# Backplane.net
KiCad netlist of a schematic drawn in EAGLE
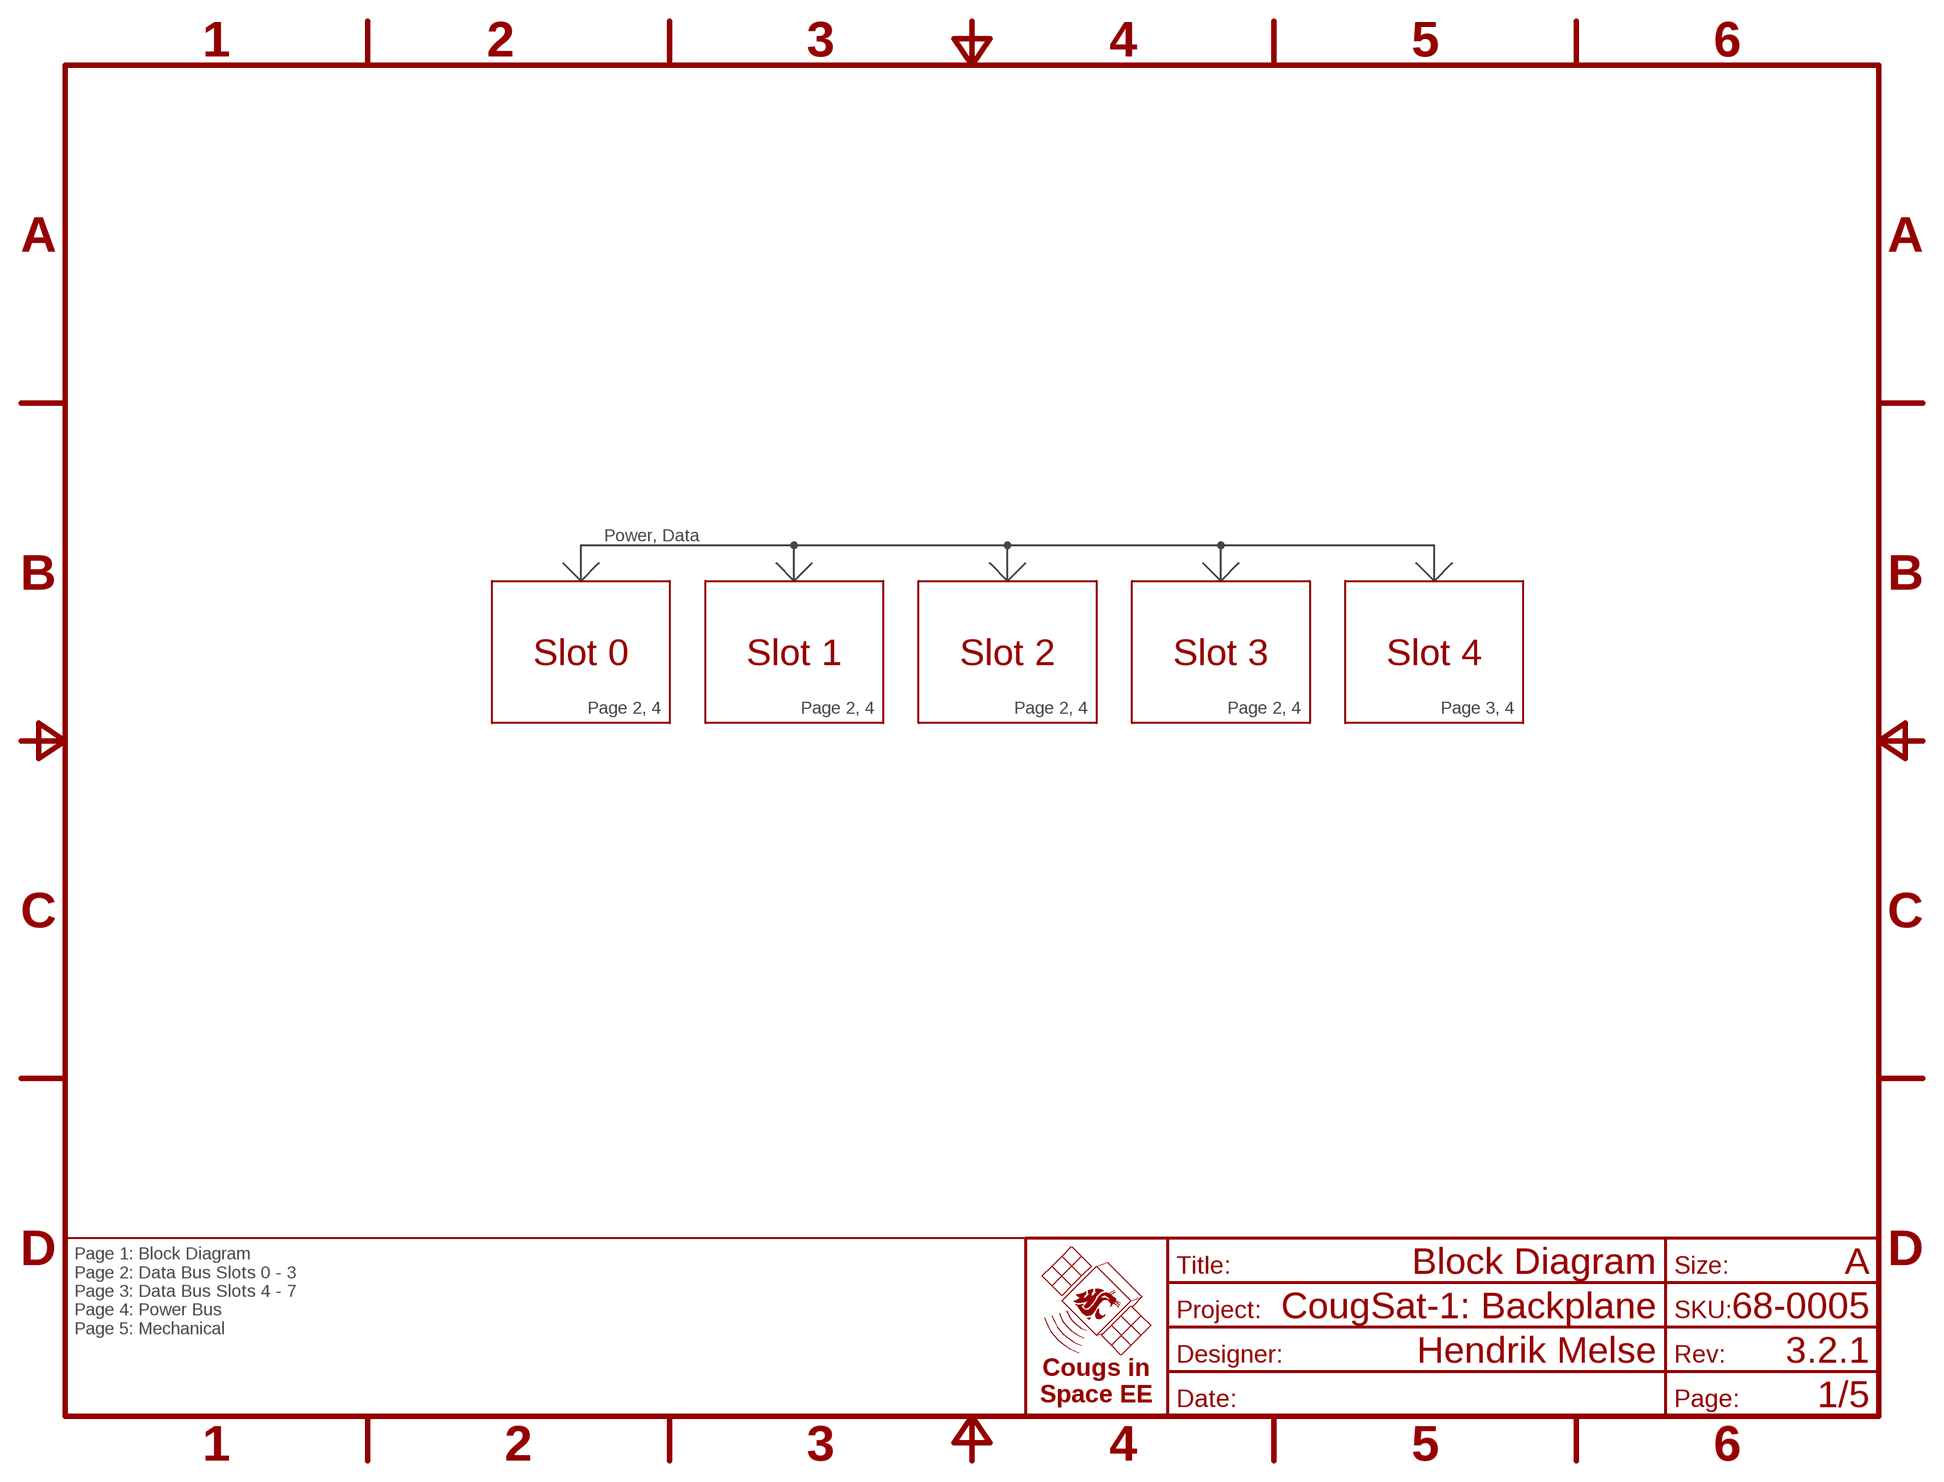
[diagram p0: schematic, sheet 1]
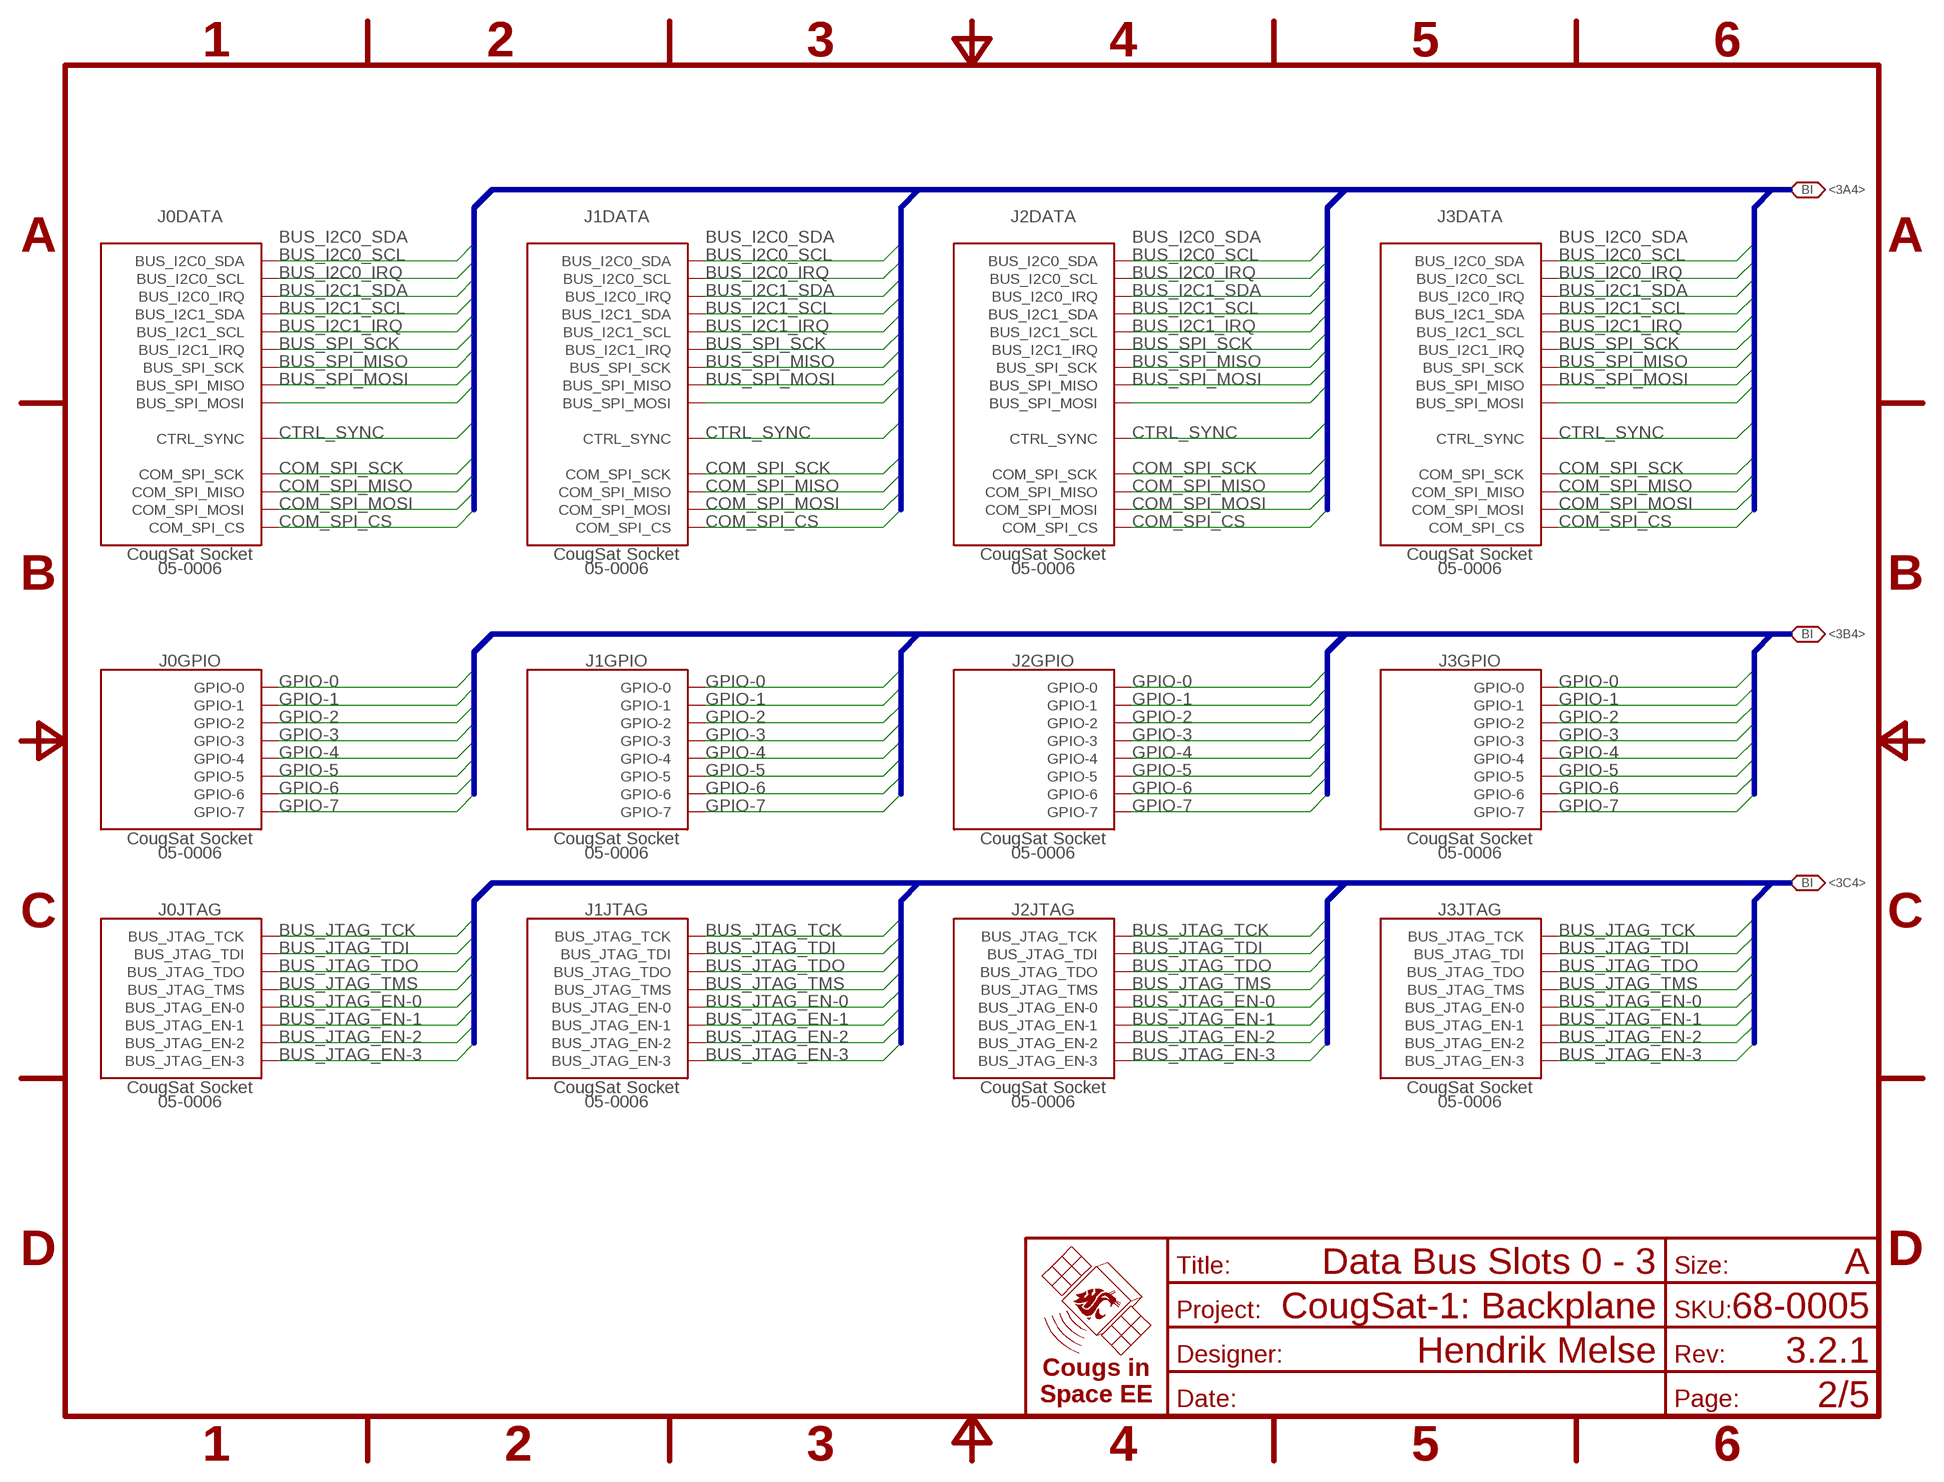
[diagram p1: schematic, sheet 2]
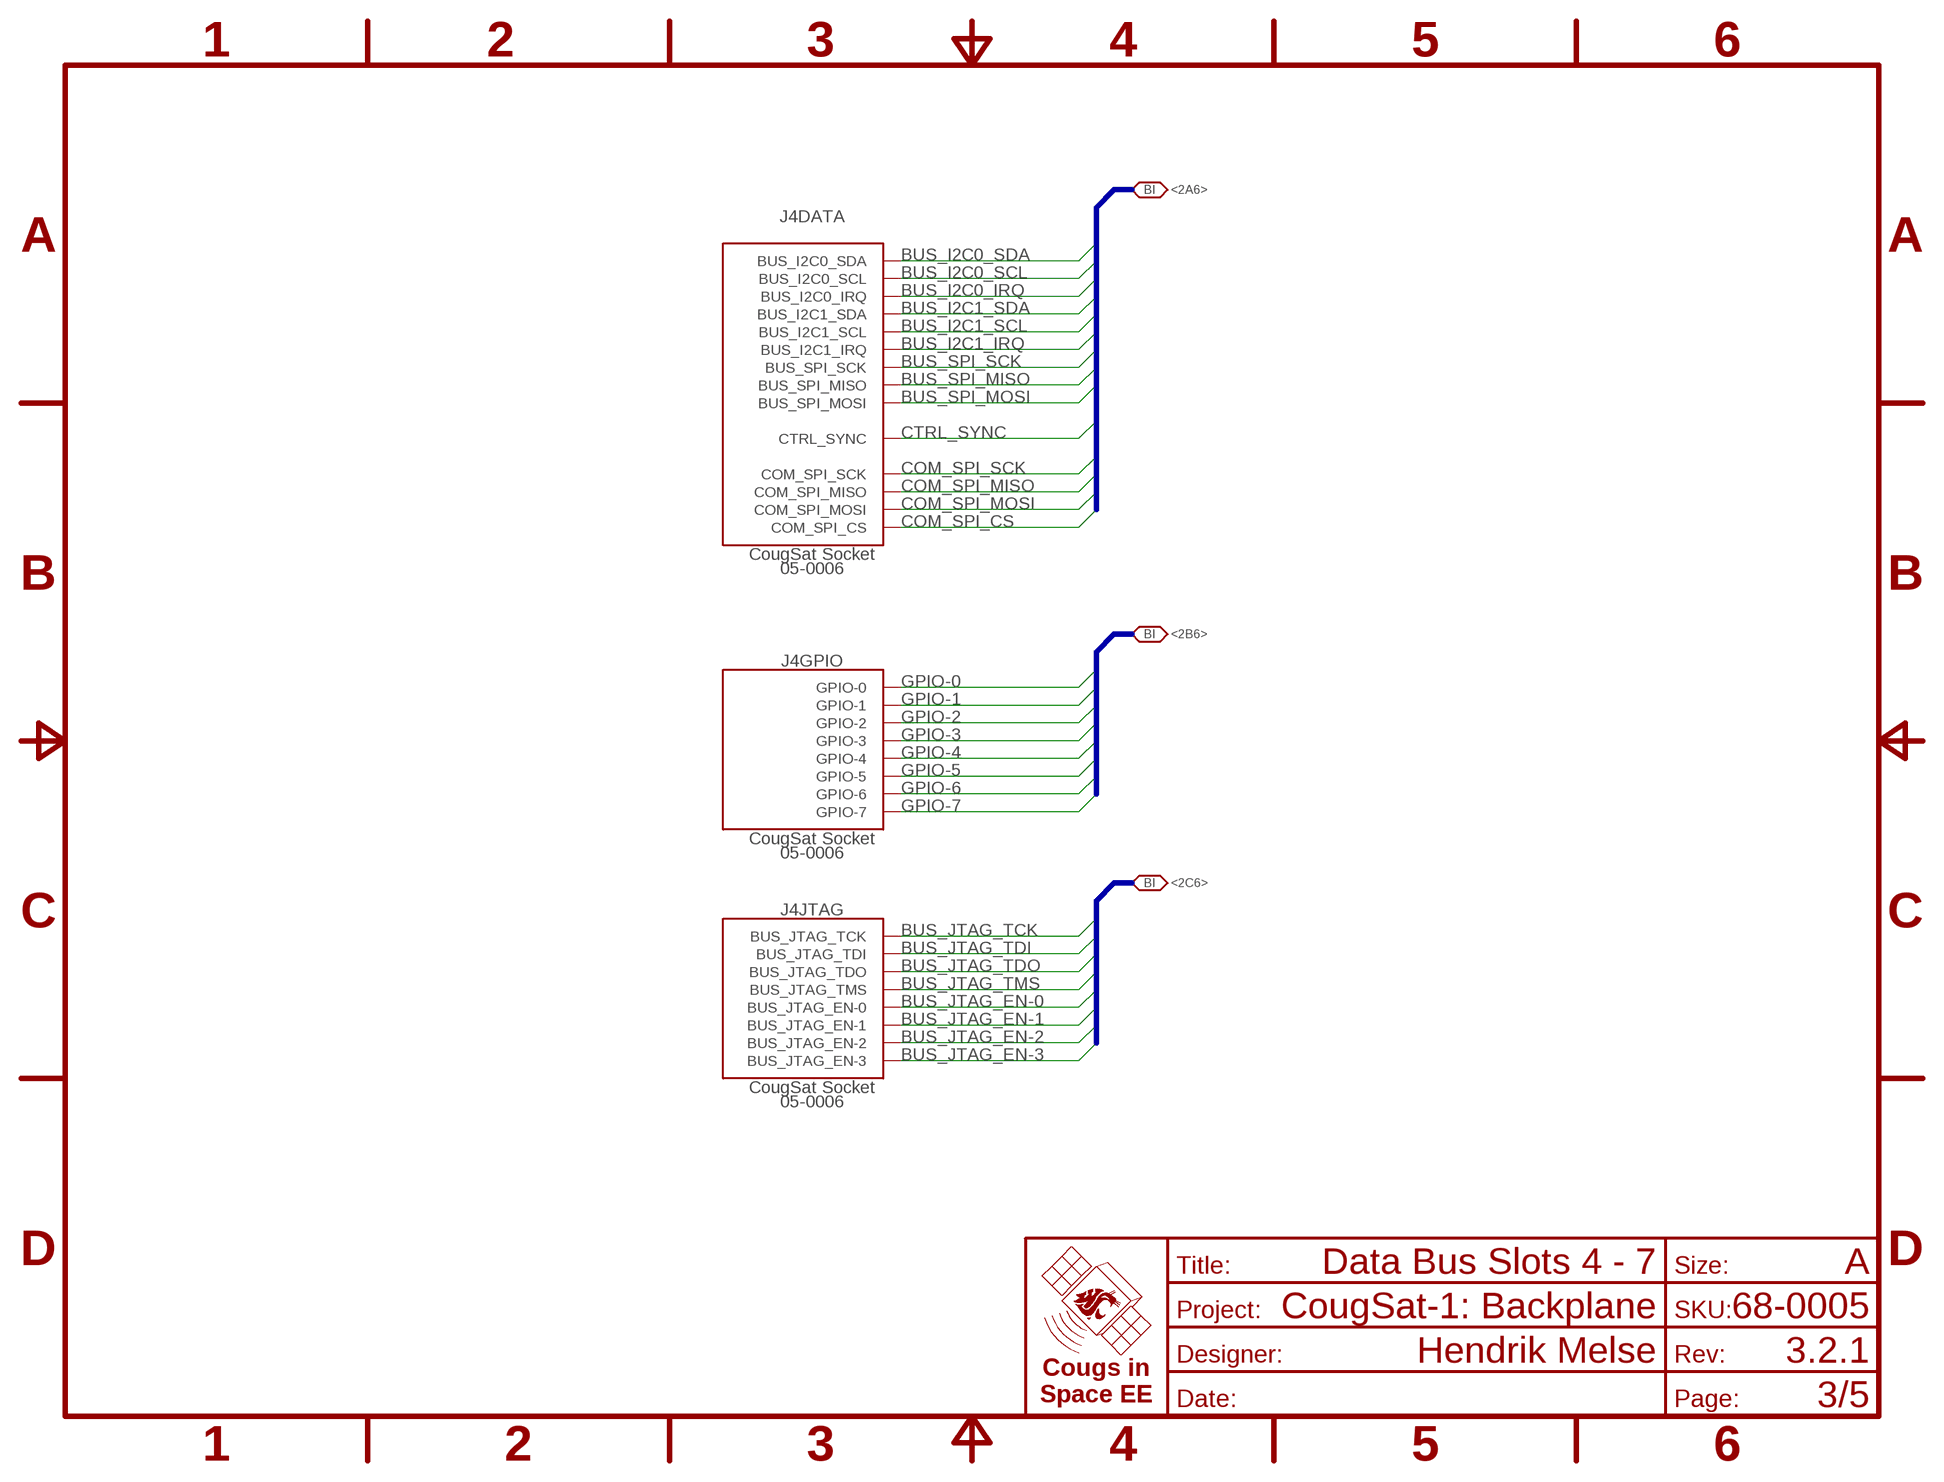
[diagram p2: schematic, sheet 3]
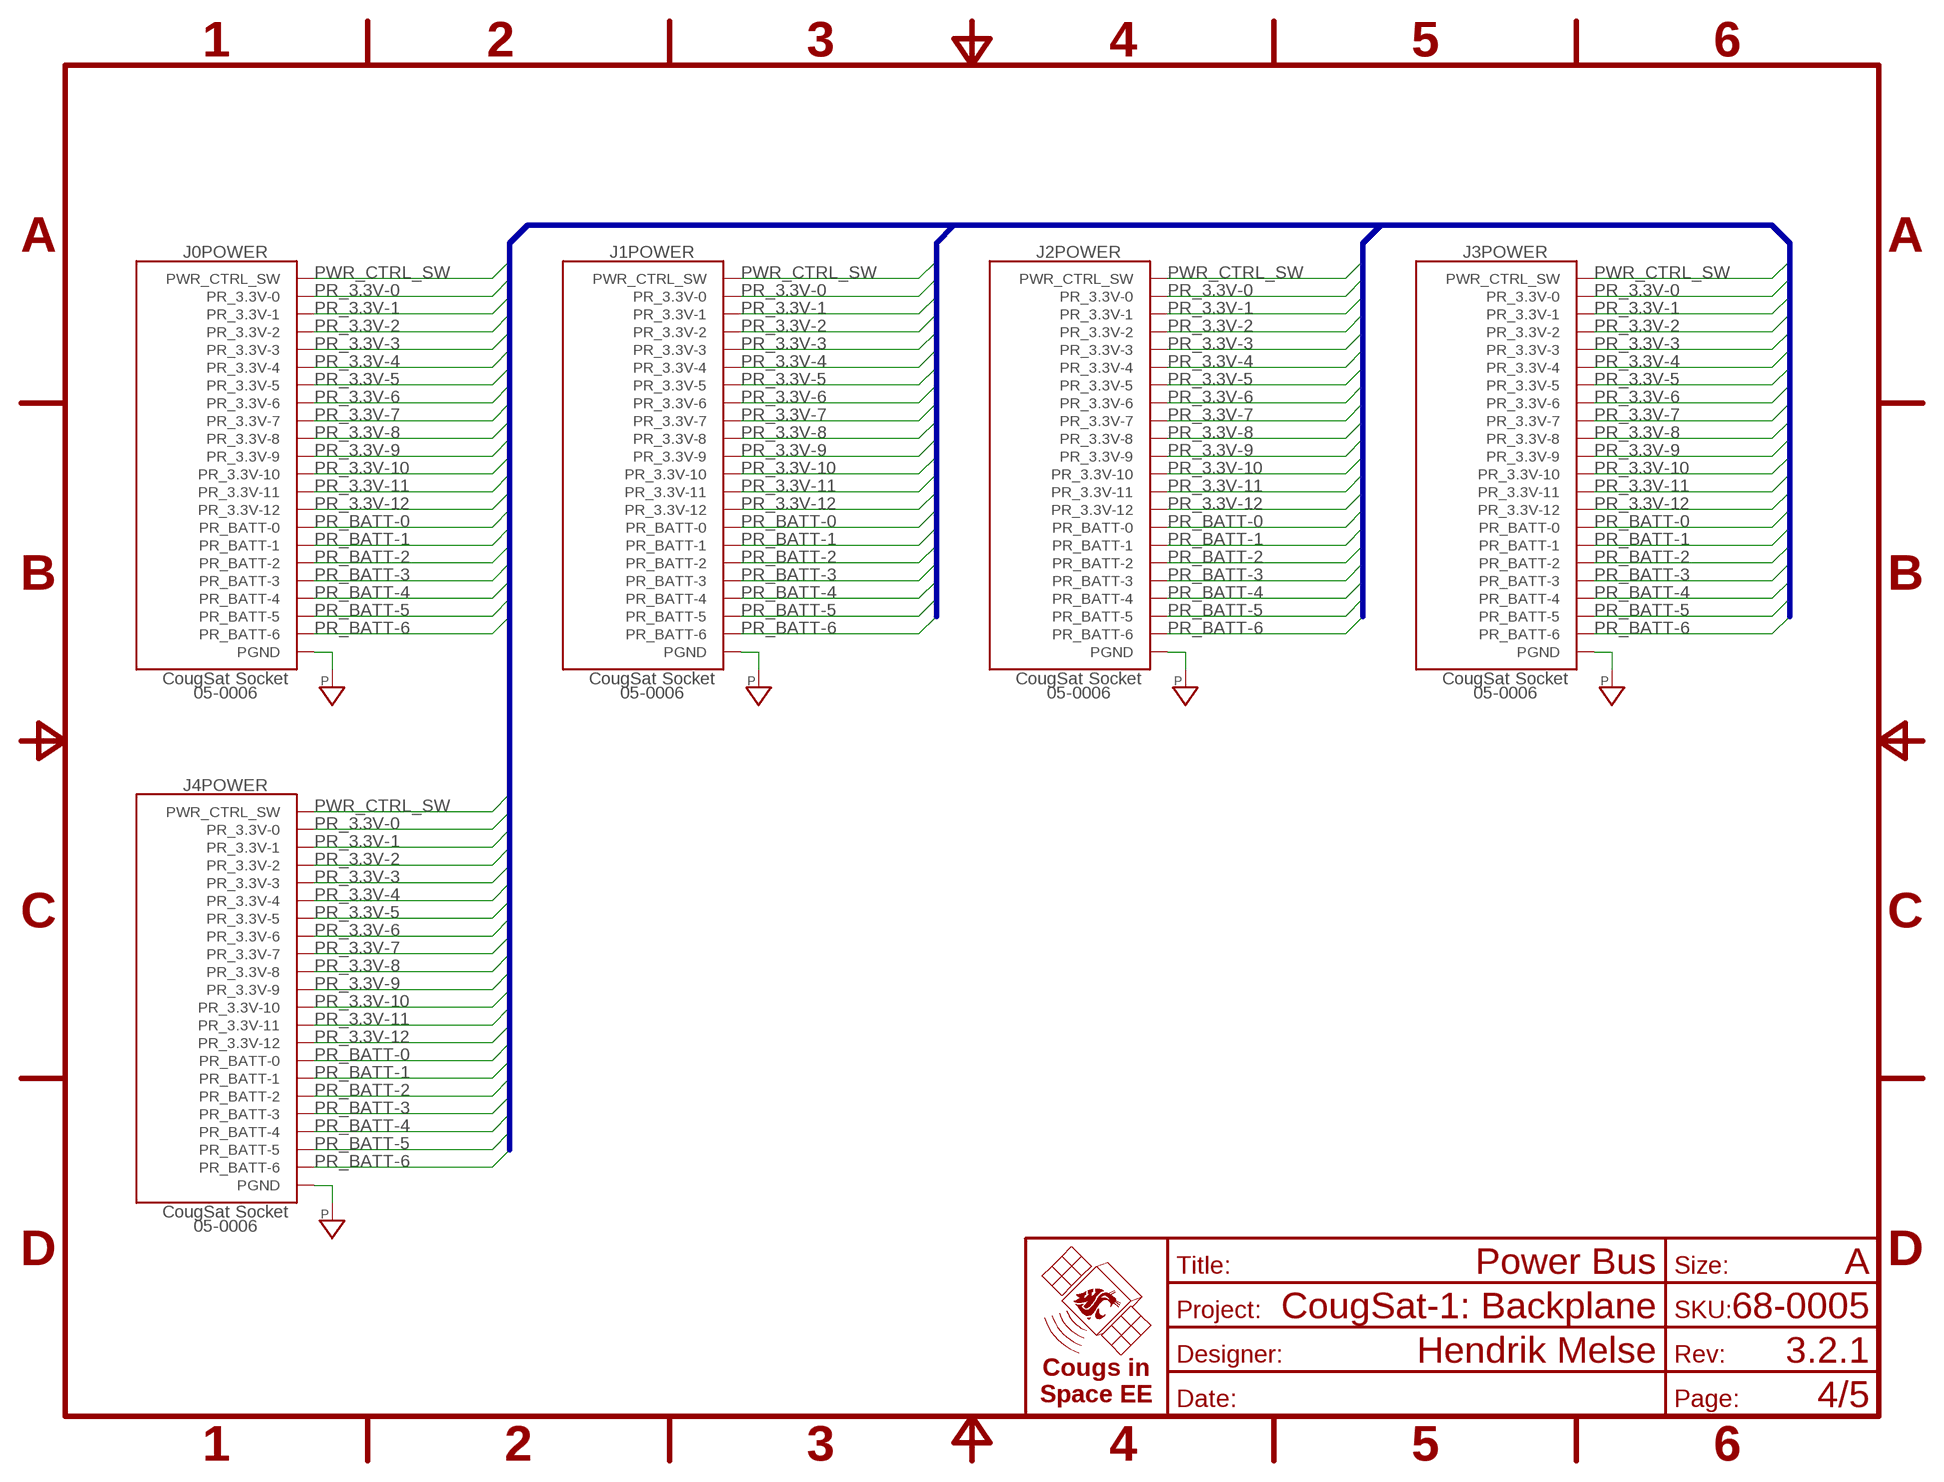
[diagram p3: schematic, sheet 4]
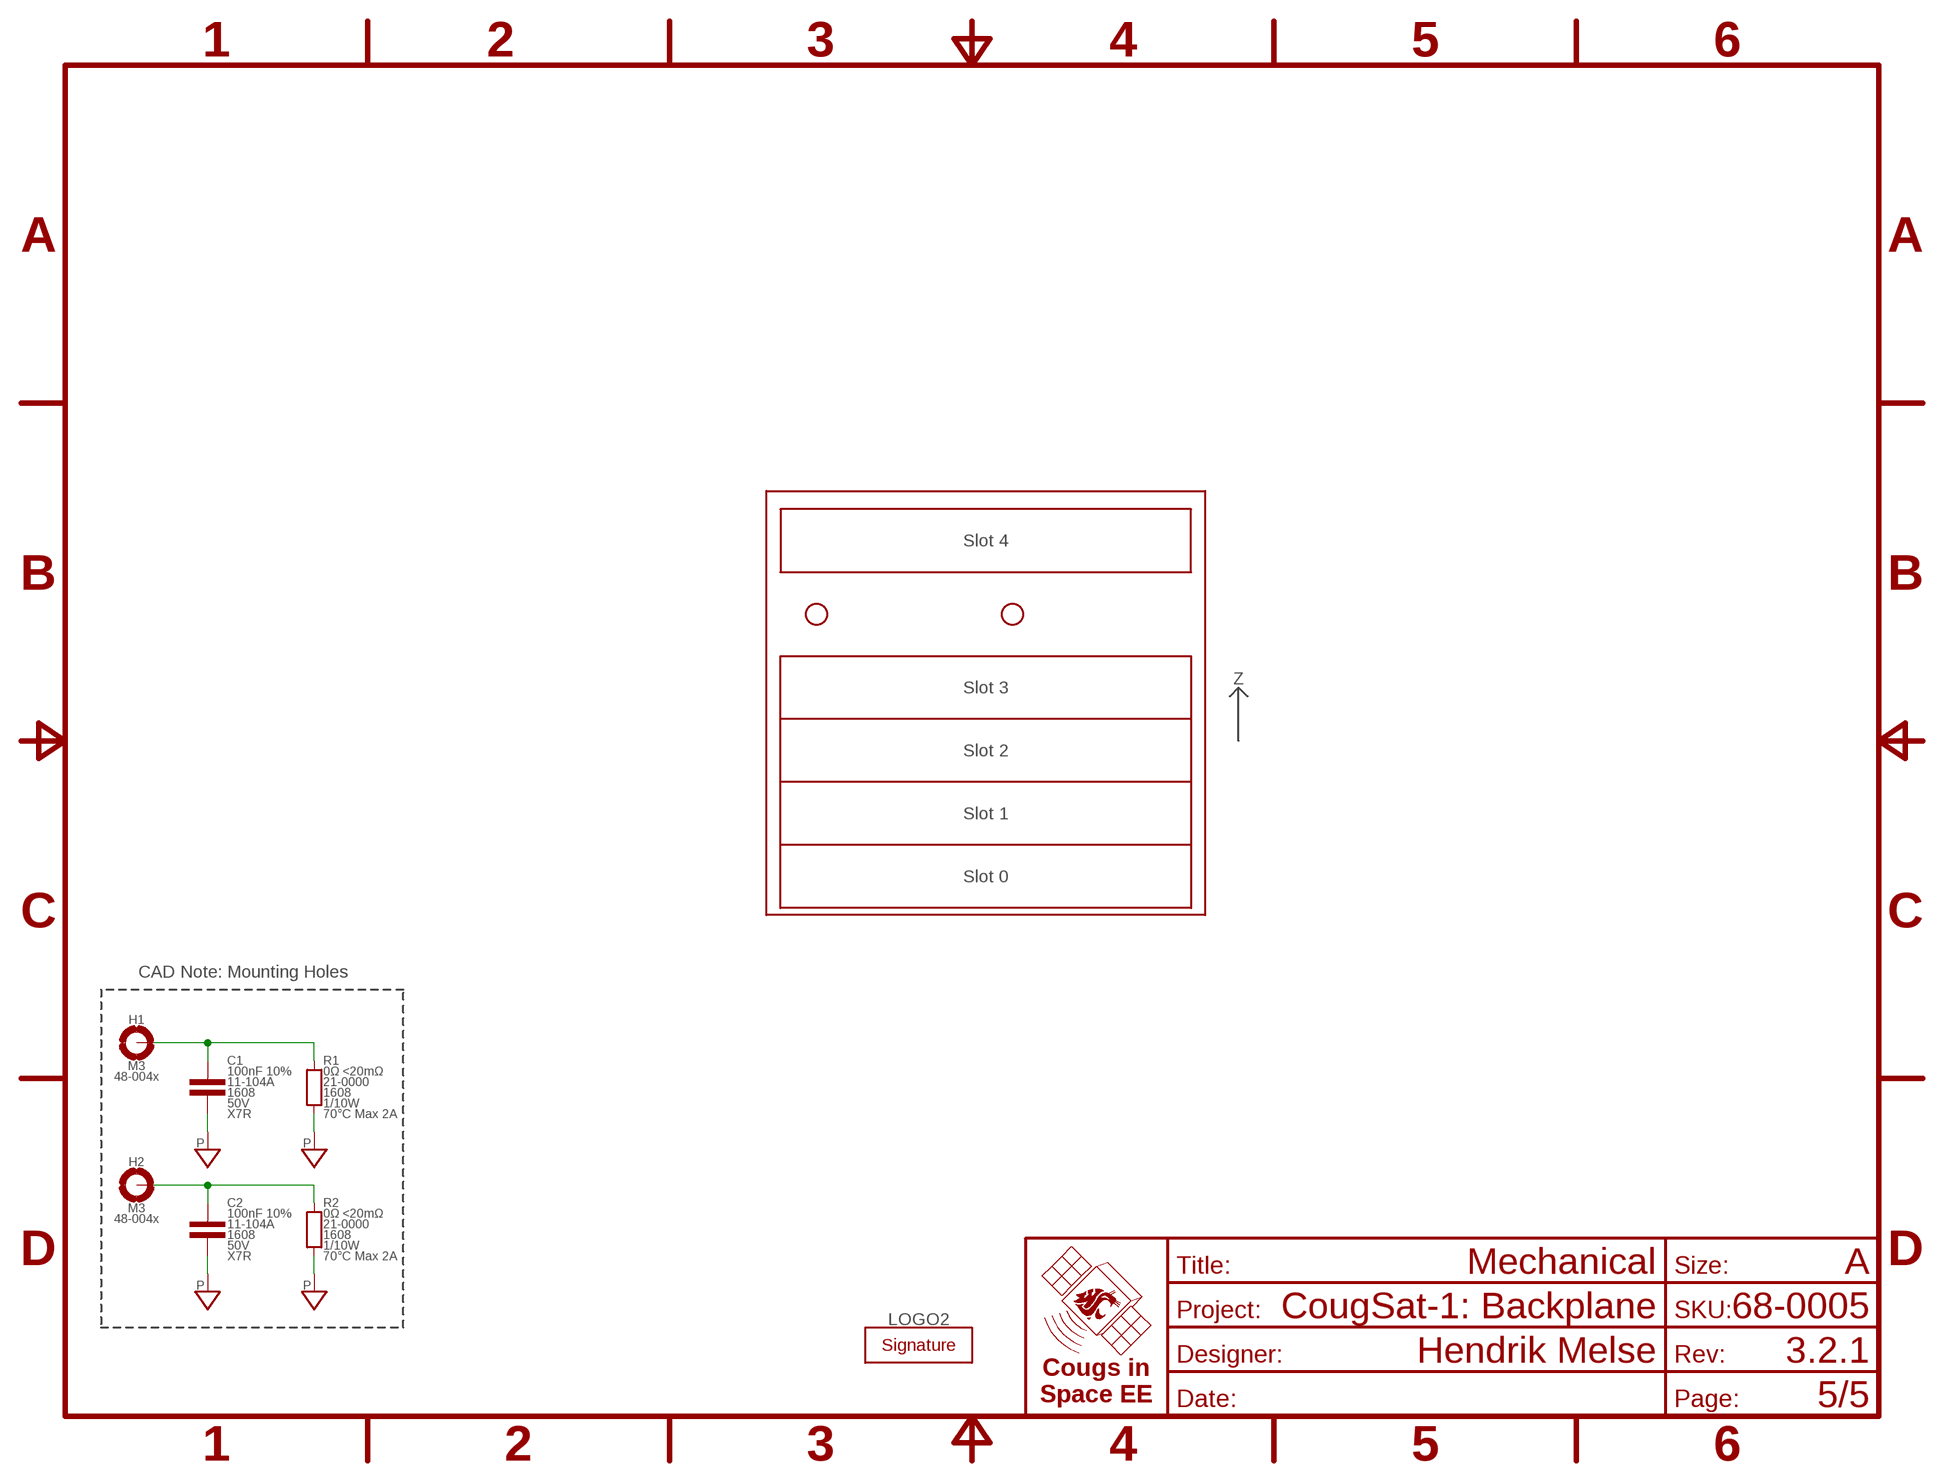
[diagram p4: schematic, sheet 5]

(export (version "E")
  (design (tool "Eeschema 10.0.6"))
  (components
    (comp (ref "J0")
      (value "CougSat Socket")
      (footprint "eagle-import:PCIE-8")
      (libsource (lib "eagle-import") (part "CIS_CARD-PCIE"))
    )
    (comp (ref "J1")
      (value "CougSat Socket")
      (footprint "eagle-import:PCIE-8")
      (libsource (lib "eagle-import") (part "CIS_CARD-PCIE"))
    )
    (comp (ref "J2")
      (value "CougSat Socket")
      (footprint "eagle-import:PCIE-8")
      (libsource (lib "eagle-import") (part "CIS_CARD-PCIE"))
    )
    (comp (ref "J3")
      (value "CougSat Socket")
      (footprint "eagle-import:PCIE-8")
      (libsource (lib "eagle-import") (part "CIS_CARD-PCIE"))
    )
    (comp (ref "C1")
      (value "100nF 10%")
      (footprint "eagle-import:1608")
      (fields
        (field (name "PACKAGE") "1608")
        (field (name "SKU") "11-104A")
        (field (name "TEMP") "X7R")
        (field (name "VOLTAGE") "50V")
      )
      (libsource (lib "eagle-import") (part "CAP-V-1608-100NF"))
    )
    (comp (ref "C2")
      (value "100nF 10%")
      (footprint "eagle-import:1608")
      (fields
        (field (name "PACKAGE") "1608")
        (field (name "SKU") "11-104A")
        (field (name "TEMP") "X7R")
        (field (name "VOLTAGE") "50V")
      )
      (libsource (lib "eagle-import") (part "CAP-V-1608-100NF"))
    )
    (comp (ref "H1")
      (value "M3")
      (footprint "eagle-import:MOUNTING_HOLE-3.3")
      (fields (field (name "SKU") "48-004x"))
      (libsource (lib "eagle-import") (part "MOUNTING_HOLE-3.3"))
    )
    (comp (ref "H2")
      (value "M3")
      (footprint "eagle-import:MOUNTING_HOLE-3.3")
      (fields (field (name "SKU") "48-004x"))
      (libsource (lib "eagle-import") (part "MOUNTING_HOLE-3.3"))
    )
    (comp (ref "LOGO2")
      (value "SIGNATUREHENDRIK")
      (footprint "eagle-import:SIGN-HENDRIK")
      (libsource (lib "eagle-import") (part "SIGNATUREHENDRIK"))
    )
    (comp (ref "R1")
      (value "0Ω <20mΩ")
      (footprint "eagle-import:1608")
      (fields
        (field (name "PACKAGE") "1608")
        (field (name "POWER") "1/10W")
        (field (name "SKU") "21-0000")
        (field (name "TEMP") "70°C Max 2A")
      )
      (libsource (lib "eagle-import") (part "RES-V-1608-0"))
    )
    (comp (ref "R2")
      (value "0Ω <20mΩ")
      (footprint "eagle-import:1608")
      (fields
        (field (name "PACKAGE") "1608")
        (field (name "POWER") "1/10W")
        (field (name "SKU") "21-0000")
        (field (name "TEMP") "70°C Max 2A")
      )
      (libsource (lib "eagle-import") (part "RES-V-1608-0"))
    )
    (comp (ref "J4")
      (value "CougSat Socket")
      (footprint "eagle-import:PCIE-8")
      (libsource (lib "eagle-import") (part "CIS_CARD-PCIE"))
    )
  )
  (nets
    (net (code "1") (name "BUS_I2C0_IRQ") (class "Default")
      (node (ref "J0") (pin "A45") (pinfunction "BUS_I2C0_IRQ_A45") (pintype "bidirectional"))
      (node (ref "J0") (pin "B45") (pinfunction "BUS_I2C0_IRQ_B45") (pintype "bidirectional"))
      (node (ref "J1") (pin "A45") (pinfunction "BUS_I2C0_IRQ_A45") (pintype "bidirectional"))
      (node (ref "J1") (pin "B45") (pinfunction "BUS_I2C0_IRQ_B45") (pintype "bidirectional"))
      (node (ref "J2") (pin "A45") (pinfunction "BUS_I2C0_IRQ_A45") (pintype "bidirectional"))
      (node (ref "J2") (pin "B45") (pinfunction "BUS_I2C0_IRQ_B45") (pintype "bidirectional"))
      (node (ref "J3") (pin "A45") (pinfunction "BUS_I2C0_IRQ_A45") (pintype "bidirectional"))
      (node (ref "J3") (pin "B45") (pinfunction "BUS_I2C0_IRQ_B45") (pintype "bidirectional"))
      (node (ref "J4") (pin "A45") (pinfunction "BUS_I2C0_IRQ_A45") (pintype "bidirectional"))
      (node (ref "J4") (pin "B45") (pinfunction "BUS_I2C0_IRQ_B45") (pintype "bidirectional"))
    )
    (net (code "2") (name "BUS_I2C0_SCL") (class "Default")
      (node (ref "J0") (pin "A44") (pinfunction "BUS_I2C0_SCL_A44") (pintype "bidirectional"))
      (node (ref "J0") (pin "B44") (pinfunction "BUS_I2C0_SCL_B44") (pintype "bidirectional"))
      (node (ref "J1") (pin "A44") (pinfunction "BUS_I2C0_SCL_A44") (pintype "bidirectional"))
      (node (ref "J1") (pin "B44") (pinfunction "BUS_I2C0_SCL_B44") (pintype "bidirectional"))
      (node (ref "J2") (pin "A44") (pinfunction "BUS_I2C0_SCL_A44") (pintype "bidirectional"))
      (node (ref "J2") (pin "B44") (pinfunction "BUS_I2C0_SCL_B44") (pintype "bidirectional"))
      (node (ref "J3") (pin "A44") (pinfunction "BUS_I2C0_SCL_A44") (pintype "bidirectional"))
      (node (ref "J3") (pin "B44") (pinfunction "BUS_I2C0_SCL_B44") (pintype "bidirectional"))
      (node (ref "J4") (pin "A44") (pinfunction "BUS_I2C0_SCL_A44") (pintype "bidirectional"))
      (node (ref "J4") (pin "B44") (pinfunction "BUS_I2C0_SCL_B44") (pintype "bidirectional"))
    )
    (net (code "3") (name "BUS_I2C0_SDA") (class "Default")
      (node (ref "J0") (pin "A43") (pinfunction "BUS_I2C0_SDA_A43") (pintype "bidirectional"))
      (node (ref "J0") (pin "B43") (pinfunction "BUS_I2C0_SDA_B43") (pintype "bidirectional"))
      (node (ref "J1") (pin "A43") (pinfunction "BUS_I2C0_SDA_A43") (pintype "bidirectional"))
      (node (ref "J1") (pin "B43") (pinfunction "BUS_I2C0_SDA_B43") (pintype "bidirectional"))
      (node (ref "J2") (pin "A43") (pinfunction "BUS_I2C0_SDA_A43") (pintype "bidirectional"))
      (node (ref "J2") (pin "B43") (pinfunction "BUS_I2C0_SDA_B43") (pintype "bidirectional"))
      (node (ref "J3") (pin "A43") (pinfunction "BUS_I2C0_SDA_A43") (pintype "bidirectional"))
      (node (ref "J3") (pin "B43") (pinfunction "BUS_I2C0_SDA_B43") (pintype "bidirectional"))
      (node (ref "J4") (pin "A43") (pinfunction "BUS_I2C0_SDA_A43") (pintype "bidirectional"))
      (node (ref "J4") (pin "B43") (pinfunction "BUS_I2C0_SDA_B43") (pintype "bidirectional"))
    )
    (net (code "4") (name "BUS_I2C1_IRQ") (class "Default")
      (node (ref "J0") (pin "A32") (pinfunction "BUS_I2C1_IRQ_A32") (pintype "bidirectional"))
      (node (ref "J0") (pin "B32") (pinfunction "BUS_I2C1_IRQ_B32") (pintype "bidirectional"))
      (node (ref "J1") (pin "A32") (pinfunction "BUS_I2C1_IRQ_A32") (pintype "bidirectional"))
      (node (ref "J1") (pin "B32") (pinfunction "BUS_I2C1_IRQ_B32") (pintype "bidirectional"))
      (node (ref "J2") (pin "A32") (pinfunction "BUS_I2C1_IRQ_A32") (pintype "bidirectional"))
      (node (ref "J2") (pin "B32") (pinfunction "BUS_I2C1_IRQ_B32") (pintype "bidirectional"))
      (node (ref "J3") (pin "A32") (pinfunction "BUS_I2C1_IRQ_A32") (pintype "bidirectional"))
      (node (ref "J3") (pin "B32") (pinfunction "BUS_I2C1_IRQ_B32") (pintype "bidirectional"))
      (node (ref "J4") (pin "A32") (pinfunction "BUS_I2C1_IRQ_A32") (pintype "bidirectional"))
      (node (ref "J4") (pin "B32") (pinfunction "BUS_I2C1_IRQ_B32") (pintype "bidirectional"))
    )
    (net (code "5") (name "BUS_I2C1_SCL") (class "Default")
      (node (ref "J0") (pin "A31") (pinfunction "BUS_I2C1_SCL_A31") (pintype "bidirectional"))
      (node (ref "J0") (pin "B31") (pinfunction "BUS_I2C1_SCL_B31") (pintype "bidirectional"))
      (node (ref "J1") (pin "A31") (pinfunction "BUS_I2C1_SCL_A31") (pintype "bidirectional"))
      (node (ref "J1") (pin "B31") (pinfunction "BUS_I2C1_SCL_B31") (pintype "bidirectional"))
      (node (ref "J2") (pin "A31") (pinfunction "BUS_I2C1_SCL_A31") (pintype "bidirectional"))
      (node (ref "J2") (pin "B31") (pinfunction "BUS_I2C1_SCL_B31") (pintype "bidirectional"))
      (node (ref "J3") (pin "A31") (pinfunction "BUS_I2C1_SCL_A31") (pintype "bidirectional"))
      (node (ref "J3") (pin "B31") (pinfunction "BUS_I2C1_SCL_B31") (pintype "bidirectional"))
      (node (ref "J4") (pin "A31") (pinfunction "BUS_I2C1_SCL_A31") (pintype "bidirectional"))
      (node (ref "J4") (pin "B31") (pinfunction "BUS_I2C1_SCL_B31") (pintype "bidirectional"))
    )
    (net (code "6") (name "BUS_I2C1_SDA") (class "Default")
      (node (ref "J0") (pin "A30") (pinfunction "BUS_I2C1_SDA_A30") (pintype "bidirectional"))
      (node (ref "J0") (pin "B30") (pinfunction "BUS_I2C1_SDA_B30") (pintype "bidirectional"))
      (node (ref "J1") (pin "A30") (pinfunction "BUS_I2C1_SDA_A30") (pintype "bidirectional"))
      (node (ref "J1") (pin "B30") (pinfunction "BUS_I2C1_SDA_B30") (pintype "bidirectional"))
      (node (ref "J2") (pin "A30") (pinfunction "BUS_I2C1_SDA_A30") (pintype "bidirectional"))
      (node (ref "J2") (pin "B30") (pinfunction "BUS_I2C1_SDA_B30") (pintype "bidirectional"))
      (node (ref "J3") (pin "A30") (pinfunction "BUS_I2C1_SDA_A30") (pintype "bidirectional"))
      (node (ref "J3") (pin "B30") (pinfunction "BUS_I2C1_SDA_B30") (pintype "bidirectional"))
      (node (ref "J4") (pin "A30") (pinfunction "BUS_I2C1_SDA_A30") (pintype "bidirectional"))
      (node (ref "J4") (pin "B30") (pinfunction "BUS_I2C1_SDA_B30") (pintype "bidirectional"))
    )
    (net (code "7") (name "BUS_JTAG_EN-0") (class "Default")
      (node (ref "J0") (pin "B46") (pinfunction "BUS_JTAG_EN-0_B46") (pintype "bidirectional"))
      (node (ref "J1") (pin "B46") (pinfunction "BUS_JTAG_EN-0_B46") (pintype "bidirectional"))
      (node (ref "J2") (pin "B46") (pinfunction "BUS_JTAG_EN-0_B46") (pintype "bidirectional"))
      (node (ref "J3") (pin "B46") (pinfunction "BUS_JTAG_EN-0_B46") (pintype "bidirectional"))
      (node (ref "J4") (pin "B46") (pinfunction "BUS_JTAG_EN-0_B46") (pintype "bidirectional"))
    )
    (net (code "8") (name "BUS_JTAG_EN-1") (class "Default")
      (node (ref "J0") (pin "B47") (pinfunction "BUS_JTAG_EN-1_B47") (pintype "bidirectional"))
      (node (ref "J1") (pin "B47") (pinfunction "BUS_JTAG_EN-1_B47") (pintype "bidirectional"))
      (node (ref "J2") (pin "B47") (pinfunction "BUS_JTAG_EN-1_B47") (pintype "bidirectional"))
      (node (ref "J3") (pin "B47") (pinfunction "BUS_JTAG_EN-1_B47") (pintype "bidirectional"))
      (node (ref "J4") (pin "B47") (pinfunction "BUS_JTAG_EN-1_B47") (pintype "bidirectional"))
    )
    (net (code "9") (name "BUS_JTAG_EN-2") (class "Default")
      (node (ref "J0") (pin "B48") (pinfunction "BUS_JTAG_EN-2_B48") (pintype "bidirectional"))
      (node (ref "J1") (pin "B48") (pinfunction "BUS_JTAG_EN-2_B48") (pintype "bidirectional"))
      (node (ref "J2") (pin "B48") (pinfunction "BUS_JTAG_EN-2_B48") (pintype "bidirectional"))
      (node (ref "J3") (pin "B48") (pinfunction "BUS_JTAG_EN-2_B48") (pintype "bidirectional"))
      (node (ref "J4") (pin "B48") (pinfunction "BUS_JTAG_EN-2_B48") (pintype "bidirectional"))
    )
    (net (code "10") (name "BUS_JTAG_EN-3") (class "Default")
      (node (ref "J0") (pin "B49") (pinfunction "BUS_JTAG_EN-3_B49") (pintype "bidirectional"))
      (node (ref "J1") (pin "B49") (pinfunction "BUS_JTAG_EN-3_B49") (pintype "bidirectional"))
      (node (ref "J2") (pin "B49") (pinfunction "BUS_JTAG_EN-3_B49") (pintype "bidirectional"))
      (node (ref "J3") (pin "B49") (pinfunction "BUS_JTAG_EN-3_B49") (pintype "bidirectional"))
      (node (ref "J4") (pin "B49") (pinfunction "BUS_JTAG_EN-3_B49") (pintype "bidirectional"))
    )
    (net (code "11") (name "BUS_JTAG_TCK") (class "Default")
      (node (ref "J0") (pin "A46") (pinfunction "BUS_JTAG_TCK_A46") (pintype "bidirectional"))
      (node (ref "J1") (pin "A46") (pinfunction "BUS_JTAG_TCK_A46") (pintype "bidirectional"))
      (node (ref "J2") (pin "A46") (pinfunction "BUS_JTAG_TCK_A46") (pintype "bidirectional"))
      (node (ref "J3") (pin "A46") (pinfunction "BUS_JTAG_TCK_A46") (pintype "bidirectional"))
      (node (ref "J4") (pin "A46") (pinfunction "BUS_JTAG_TCK_A46") (pintype "bidirectional"))
    )
    (net (code "12") (name "BUS_JTAG_TDI") (class "Default")
      (node (ref "J0") (pin "A47") (pinfunction "BUS_JTAG_TDI_A47") (pintype "bidirectional"))
      (node (ref "J1") (pin "A47") (pinfunction "BUS_JTAG_TDI_A47") (pintype "bidirectional"))
      (node (ref "J2") (pin "A47") (pinfunction "BUS_JTAG_TDI_A47") (pintype "bidirectional"))
      (node (ref "J3") (pin "A47") (pinfunction "BUS_JTAG_TDI_A47") (pintype "bidirectional"))
      (node (ref "J4") (pin "A47") (pinfunction "BUS_JTAG_TDI_A47") (pintype "bidirectional"))
    )
    (net (code "13") (name "BUS_JTAG_TDO") (class "Default")
      (node (ref "J0") (pin "A48") (pinfunction "BUS_JTAG_TDO_A48") (pintype "bidirectional"))
      (node (ref "J1") (pin "A48") (pinfunction "BUS_JTAG_TDO_A48") (pintype "bidirectional"))
      (node (ref "J2") (pin "A48") (pinfunction "BUS_JTAG_TDO_A48") (pintype "bidirectional"))
      (node (ref "J3") (pin "A48") (pinfunction "BUS_JTAG_TDO_A48") (pintype "bidirectional"))
      (node (ref "J4") (pin "A48") (pinfunction "BUS_JTAG_TDO_A48") (pintype "bidirectional"))
    )
    (net (code "14") (name "BUS_JTAG_TMS") (class "Default")
      (node (ref "J0") (pin "A49") (pinfunction "BUS_JTAG_TMS_A49") (pintype "bidirectional"))
      (node (ref "J1") (pin "A49") (pinfunction "BUS_JTAG_TMS_A49") (pintype "bidirectional"))
      (node (ref "J2") (pin "A49") (pinfunction "BUS_JTAG_TMS_A49") (pintype "bidirectional"))
      (node (ref "J3") (pin "A49") (pinfunction "BUS_JTAG_TMS_A49") (pintype "bidirectional"))
      (node (ref "J4") (pin "A49") (pinfunction "BUS_JTAG_TMS_A49") (pintype "bidirectional"))
    )
    (net (code "15") (name "BUS_SPI_MISO") (class "Default")
      (node (ref "J0") (pin "A38") (pinfunction "BUS_SPI_MISO_A38") (pintype "bidirectional"))
      (node (ref "J0") (pin "B38") (pinfunction "BUS_SPI_MISO_B38") (pintype "bidirectional"))
      (node (ref "J1") (pin "A38") (pinfunction "BUS_SPI_MISO_A38") (pintype "bidirectional"))
      (node (ref "J1") (pin "B38") (pinfunction "BUS_SPI_MISO_B38") (pintype "bidirectional"))
      (node (ref "J2") (pin "A38") (pinfunction "BUS_SPI_MISO_A38") (pintype "bidirectional"))
      (node (ref "J2") (pin "B38") (pinfunction "BUS_SPI_MISO_B38") (pintype "bidirectional"))
      (node (ref "J3") (pin "A38") (pinfunction "BUS_SPI_MISO_A38") (pintype "bidirectional"))
      (node (ref "J3") (pin "B38") (pinfunction "BUS_SPI_MISO_B38") (pintype "bidirectional"))
      (node (ref "J4") (pin "A38") (pinfunction "BUS_SPI_MISO_A38") (pintype "bidirectional"))
      (node (ref "J4") (pin "B38") (pinfunction "BUS_SPI_MISO_B38") (pintype "bidirectional"))
    )
    (net (code "16") (name "BUS_SPI_MOSI") (class "Default")
      (node (ref "J0") (pin "A39") (pinfunction "BUS_SPI_MOSI_A39") (pintype "bidirectional"))
      (node (ref "J0") (pin "B39") (pinfunction "BUS_SPI_MOSI_B39") (pintype "bidirectional"))
      (node (ref "J1") (pin "A39") (pinfunction "BUS_SPI_MOSI_A39") (pintype "bidirectional"))
      (node (ref "J1") (pin "B39") (pinfunction "BUS_SPI_MOSI_B39") (pintype "bidirectional"))
      (node (ref "J2") (pin "A39") (pinfunction "BUS_SPI_MOSI_A39") (pintype "bidirectional"))
      (node (ref "J2") (pin "B39") (pinfunction "BUS_SPI_MOSI_B39") (pintype "bidirectional"))
      (node (ref "J3") (pin "A39") (pinfunction "BUS_SPI_MOSI_A39") (pintype "bidirectional"))
      (node (ref "J3") (pin "B39") (pinfunction "BUS_SPI_MOSI_B39") (pintype "bidirectional"))
      (node (ref "J4") (pin "A39") (pinfunction "BUS_SPI_MOSI_A39") (pintype "bidirectional"))
      (node (ref "J4") (pin "B39") (pinfunction "BUS_SPI_MOSI_B39") (pintype "bidirectional"))
    )
    (net (code "17") (name "BUS_SPI_SCK") (class "Default")
      (node (ref "J0") (pin "A37") (pinfunction "BUS_SPI_SCK_A37") (pintype "bidirectional"))
      (node (ref "J0") (pin "B37") (pinfunction "BUS_SPI_SCK_B37") (pintype "bidirectional"))
      (node (ref "J1") (pin "A37") (pinfunction "BUS_SPI_SCK_A37") (pintype "bidirectional"))
      (node (ref "J1") (pin "B37") (pinfunction "BUS_SPI_SCK_B37") (pintype "bidirectional"))
      (node (ref "J2") (pin "A37") (pinfunction "BUS_SPI_SCK_A37") (pintype "bidirectional"))
      (node (ref "J2") (pin "B37") (pinfunction "BUS_SPI_SCK_B37") (pintype "bidirectional"))
      (node (ref "J3") (pin "A37") (pinfunction "BUS_SPI_SCK_A37") (pintype "bidirectional"))
      (node (ref "J3") (pin "B37") (pinfunction "BUS_SPI_SCK_B37") (pintype "bidirectional"))
      (node (ref "J4") (pin "A37") (pinfunction "BUS_SPI_SCK_A37") (pintype "bidirectional"))
      (node (ref "J4") (pin "B37") (pinfunction "BUS_SPI_SCK_B37") (pintype "bidirectional"))
    )
    (net (code "18") (name "COM_SPI_CS") (class "Default")
      (node (ref "J0") (pin "A36") (pinfunction "COM_SPI_CS_A36") (pintype "bidirectional"))
      (node (ref "J0") (pin "B36") (pinfunction "COM_SPI_CS_B36") (pintype "bidirectional"))
      (node (ref "J1") (pin "A36") (pinfunction "COM_SPI_CS_A36") (pintype "bidirectional"))
      (node (ref "J1") (pin "B36") (pinfunction "COM_SPI_CS_B36") (pintype "bidirectional"))
      (node (ref "J2") (pin "A36") (pinfunction "COM_SPI_CS_A36") (pintype "bidirectional"))
      (node (ref "J2") (pin "B36") (pinfunction "COM_SPI_CS_B36") (pintype "bidirectional"))
      (node (ref "J3") (pin "A36") (pinfunction "COM_SPI_CS_A36") (pintype "bidirectional"))
      (node (ref "J3") (pin "B36") (pinfunction "COM_SPI_CS_B36") (pintype "bidirectional"))
      (node (ref "J4") (pin "A36") (pinfunction "COM_SPI_CS_A36") (pintype "bidirectional"))
      (node (ref "J4") (pin "B36") (pinfunction "COM_SPI_CS_B36") (pintype "bidirectional"))
    )
    (net (code "19") (name "COM_SPI_MISO") (class "Default")
      (node (ref "J0") (pin "A34") (pinfunction "COM_SPI_MISO_A34") (pintype "bidirectional"))
      (node (ref "J0") (pin "B34") (pinfunction "COM_SPI_MISO_B34") (pintype "bidirectional"))
      (node (ref "J1") (pin "A34") (pinfunction "COM_SPI_MISO_A34") (pintype "bidirectional"))
      (node (ref "J1") (pin "B34") (pinfunction "COM_SPI_MISO_B34") (pintype "bidirectional"))
      (node (ref "J2") (pin "A34") (pinfunction "COM_SPI_MISO_A34") (pintype "bidirectional"))
      (node (ref "J2") (pin "B34") (pinfunction "COM_SPI_MISO_B34") (pintype "bidirectional"))
      (node (ref "J3") (pin "A34") (pinfunction "COM_SPI_MISO_A34") (pintype "bidirectional"))
      (node (ref "J3") (pin "B34") (pinfunction "COM_SPI_MISO_B34") (pintype "bidirectional"))
      (node (ref "J4") (pin "A34") (pinfunction "COM_SPI_MISO_A34") (pintype "bidirectional"))
      (node (ref "J4") (pin "B34") (pinfunction "COM_SPI_MISO_B34") (pintype "bidirectional"))
    )
    (net (code "20") (name "COM_SPI_MOSI") (class "Default")
      (node (ref "J0") (pin "A35") (pinfunction "COM_SPI_MOSI_A35") (pintype "bidirectional"))
      (node (ref "J0") (pin "B35") (pinfunction "COM_SPI_MOSI_B35") (pintype "bidirectional"))
      (node (ref "J1") (pin "A35") (pinfunction "COM_SPI_MOSI_A35") (pintype "bidirectional"))
      (node (ref "J1") (pin "B35") (pinfunction "COM_SPI_MOSI_B35") (pintype "bidirectional"))
      (node (ref "J2") (pin "A35") (pinfunction "COM_SPI_MOSI_A35") (pintype "bidirectional"))
      (node (ref "J2") (pin "B35") (pinfunction "COM_SPI_MOSI_B35") (pintype "bidirectional"))
      (node (ref "J3") (pin "A35") (pinfunction "COM_SPI_MOSI_A35") (pintype "bidirectional"))
      (node (ref "J3") (pin "B35") (pinfunction "COM_SPI_MOSI_B35") (pintype "bidirectional"))
      (node (ref "J4") (pin "A35") (pinfunction "COM_SPI_MOSI_A35") (pintype "bidirectional"))
      (node (ref "J4") (pin "B35") (pinfunction "COM_SPI_MOSI_B35") (pintype "bidirectional"))
    )
    (net (code "21") (name "COM_SPI_SCK") (class "Default")
      (node (ref "J0") (pin "A33") (pinfunction "COM_SPI_SCK_A33") (pintype "bidirectional"))
      (node (ref "J0") (pin "B33") (pinfunction "COM_SPI_SCK_B33") (pintype "bidirectional"))
      (node (ref "J1") (pin "A33") (pinfunction "COM_SPI_SCK_A33") (pintype "bidirectional"))
      (node (ref "J1") (pin "B33") (pinfunction "COM_SPI_SCK_B33") (pintype "bidirectional"))
      (node (ref "J2") (pin "A33") (pinfunction "COM_SPI_SCK_A33") (pintype "bidirectional"))
      (node (ref "J2") (pin "B33") (pinfunction "COM_SPI_SCK_B33") (pintype "bidirectional"))
      (node (ref "J3") (pin "A33") (pinfunction "COM_SPI_SCK_A33") (pintype "bidirectional"))
      (node (ref "J3") (pin "B33") (pinfunction "COM_SPI_SCK_B33") (pintype "bidirectional"))
      (node (ref "J4") (pin "A33") (pinfunction "COM_SPI_SCK_A33") (pintype "bidirectional"))
      (node (ref "J4") (pin "B33") (pinfunction "COM_SPI_SCK_B33") (pintype "bidirectional"))
    )
    (net (code "22") (name "CTRL_SYNC") (class "Default")
      (node (ref "J0") (pin "A42") (pinfunction "CTRL_SYNC_A42") (pintype "bidirectional"))
      (node (ref "J0") (pin "B42") (pinfunction "CTRL_SYNC_B42") (pintype "bidirectional"))
      (node (ref "J1") (pin "A42") (pinfunction "CTRL_SYNC_A42") (pintype "bidirectional"))
      (node (ref "J1") (pin "B42") (pinfunction "CTRL_SYNC_B42") (pintype "bidirectional"))
      (node (ref "J2") (pin "A42") (pinfunction "CTRL_SYNC_A42") (pintype "bidirectional"))
      (node (ref "J2") (pin "B42") (pinfunction "CTRL_SYNC_B42") (pintype "bidirectional"))
      (node (ref "J3") (pin "A42") (pinfunction "CTRL_SYNC_A42") (pintype "bidirectional"))
      (node (ref "J3") (pin "B42") (pinfunction "CTRL_SYNC_B42") (pintype "bidirectional"))
      (node (ref "J4") (pin "A42") (pinfunction "CTRL_SYNC_A42") (pintype "bidirectional"))
      (node (ref "J4") (pin "B42") (pinfunction "CTRL_SYNC_B42") (pintype "bidirectional"))
    )
    (net (code "23") (name "GPIO-0") (class "Default")
      (node (ref "J0") (pin "A24") (pinfunction "GPIO-0_A24") (pintype "bidirectional"))
      (node (ref "J1") (pin "A24") (pinfunction "GPIO-0_A24") (pintype "bidirectional"))
      (node (ref "J2") (pin "A24") (pinfunction "GPIO-0_A24") (pintype "bidirectional"))
      (node (ref "J3") (pin "A24") (pinfunction "GPIO-0_A24") (pintype "bidirectional"))
      (node (ref "J4") (pin "A24") (pinfunction "GPIO-0_A24") (pintype "bidirectional"))
    )
    (net (code "24") (name "GPIO-1") (class "Default")
      (node (ref "J0") (pin "A25") (pinfunction "GPIO-1_A25") (pintype "bidirectional"))
      (node (ref "J1") (pin "A25") (pinfunction "GPIO-1_A25") (pintype "bidirectional"))
      (node (ref "J2") (pin "A25") (pinfunction "GPIO-1_A25") (pintype "bidirectional"))
      (node (ref "J3") (pin "A25") (pinfunction "GPIO-1_A25") (pintype "bidirectional"))
      (node (ref "J4") (pin "A25") (pinfunction "GPIO-1_A25") (pintype "bidirectional"))
    )
    (net (code "25") (name "GPIO-2") (class "Default")
      (node (ref "J0") (pin "A26") (pinfunction "GPIO-2_A26") (pintype "bidirectional"))
      (node (ref "J1") (pin "A26") (pinfunction "GPIO-2_A26") (pintype "bidirectional"))
      (node (ref "J2") (pin "A26") (pinfunction "GPIO-2_A26") (pintype "bidirectional"))
      (node (ref "J3") (pin "A26") (pinfunction "GPIO-2_A26") (pintype "bidirectional"))
      (node (ref "J4") (pin "A26") (pinfunction "GPIO-2_A26") (pintype "bidirectional"))
    )
    (net (code "26") (name "GPIO-3") (class "Default")
      (node (ref "J0") (pin "A27") (pinfunction "GPIO-3_A27") (pintype "bidirectional"))
      (node (ref "J1") (pin "A27") (pinfunction "GPIO-3_A27") (pintype "bidirectional"))
      (node (ref "J2") (pin "A27") (pinfunction "GPIO-3_A27") (pintype "bidirectional"))
      (node (ref "J3") (pin "A27") (pinfunction "GPIO-3_A27") (pintype "bidirectional"))
      (node (ref "J4") (pin "A27") (pinfunction "GPIO-3_A27") (pintype "bidirectional"))
    )
    (net (code "27") (name "GPIO-4") (class "Default")
      (node (ref "J0") (pin "A28") (pinfunction "GPIO-4_A28") (pintype "bidirectional"))
      (node (ref "J1") (pin "A28") (pinfunction "GPIO-4_A28") (pintype "bidirectional"))
      (node (ref "J2") (pin "A28") (pinfunction "GPIO-4_A28") (pintype "bidirectional"))
      (node (ref "J3") (pin "A28") (pinfunction "GPIO-4_A28") (pintype "bidirectional"))
      (node (ref "J4") (pin "A28") (pinfunction "GPIO-4_A28") (pintype "bidirectional"))
    )
    (net (code "28") (name "GPIO-5") (class "Default")
      (node (ref "J0") (pin "A29") (pinfunction "GPIO-5_A29") (pintype "bidirectional"))
      (node (ref "J1") (pin "A29") (pinfunction "GPIO-5_A29") (pintype "bidirectional"))
      (node (ref "J2") (pin "A29") (pinfunction "GPIO-5_A29") (pintype "bidirectional"))
      (node (ref "J3") (pin "A29") (pinfunction "GPIO-5_A29") (pintype "bidirectional"))
      (node (ref "J4") (pin "A29") (pinfunction "GPIO-5_A29") (pintype "bidirectional"))
    )
    (net (code "29") (name "GPIO-6") (class "Default")
      (node (ref "J0") (pin "A41") (pinfunction "GPIO-6_A41") (pintype "bidirectional"))
      (node (ref "J1") (pin "A41") (pinfunction "GPIO-6_A41") (pintype "bidirectional"))
      (node (ref "J2") (pin "A41") (pinfunction "GPIO-6_A41") (pintype "bidirectional"))
      (node (ref "J3") (pin "A41") (pinfunction "GPIO-6_A41") (pintype "bidirectional"))
      (node (ref "J4") (pin "A41") (pinfunction "GPIO-6_A41") (pintype "bidirectional"))
    )
    (net (code "30") (name "GPIO-7") (class "Default")
      (node (ref "J0") (pin "B41") (pinfunction "GPIO-7_B41") (pintype "bidirectional"))
      (node (ref "J1") (pin "B41") (pinfunction "GPIO-7_B41") (pintype "bidirectional"))
      (node (ref "J2") (pin "B41") (pinfunction "GPIO-7_B41") (pintype "bidirectional"))
      (node (ref "J3") (pin "B41") (pinfunction "GPIO-7_B41") (pintype "bidirectional"))
      (node (ref "J4") (pin "B41") (pinfunction "GPIO-7_B41") (pintype "bidirectional"))
    )
    (net (code "31") (name "Net-(C1-Pad1)") (class "Default")
      (node (ref "C1") (pin "1") (pinfunction "1_1") (pintype "passive"))
      (node (ref "H1") (pin "1") (pinfunction "MOUNT_1") (pintype "passive"))
      (node (ref "H1") (pin "V1") (pinfunction "MOUNT_V1") (pintype "passive"))
      (node (ref "H1") (pin "V10") (pinfunction "MOUNT_V10") (pintype "passive"))
      (node (ref "H1") (pin "V2") (pinfunction "MOUNT_V2") (pintype "passive"))
      (node (ref "H1") (pin "V3") (pinfunction "MOUNT_V3") (pintype "passive"))
      (node (ref "H1") (pin "V4") (pinfunction "MOUNT_V4") (pintype "passive"))
      (node (ref "H1") (pin "V5") (pinfunction "MOUNT_V5") (pintype "passive"))
      (node (ref "H1") (pin "V6") (pinfunction "MOUNT_V6") (pintype "passive"))
      (node (ref "H1") (pin "V7") (pinfunction "MOUNT_V7") (pintype "passive"))
      (node (ref "H1") (pin "V8") (pinfunction "MOUNT_V8") (pintype "passive"))
      (node (ref "H1") (pin "V9") (pinfunction "MOUNT_V9") (pintype "passive"))
      (node (ref "R1") (pin "2") (pinfunction "2_2") (pintype "passive"))
    )
    (net (code "32") (name "Net-(C2-Pad1)") (class "Default")
      (node (ref "C2") (pin "1") (pinfunction "1_1") (pintype "passive"))
      (node (ref "H2") (pin "1") (pinfunction "MOUNT_1") (pintype "passive"))
      (node (ref "H2") (pin "V1") (pinfunction "MOUNT_V1") (pintype "passive"))
      (node (ref "H2") (pin "V10") (pinfunction "MOUNT_V10") (pintype "passive"))
      (node (ref "H2") (pin "V2") (pinfunction "MOUNT_V2") (pintype "passive"))
      (node (ref "H2") (pin "V3") (pinfunction "MOUNT_V3") (pintype "passive"))
      (node (ref "H2") (pin "V4") (pinfunction "MOUNT_V4") (pintype "passive"))
      (node (ref "H2") (pin "V5") (pinfunction "MOUNT_V5") (pintype "passive"))
      (node (ref "H2") (pin "V6") (pinfunction "MOUNT_V6") (pintype "passive"))
      (node (ref "H2") (pin "V7") (pinfunction "MOUNT_V7") (pintype "passive"))
      (node (ref "H2") (pin "V8") (pinfunction "MOUNT_V8") (pintype "passive"))
      (node (ref "H2") (pin "V9") (pinfunction "MOUNT_V9") (pintype "passive"))
      (node (ref "R2") (pin "2") (pinfunction "2_2") (pintype "passive"))
    )
    (net (code "33") (name "PGND") (class "Default")
      (node (ref "C1") (pin "2") (pinfunction "2_2") (pintype "passive"))
      (node (ref "C2") (pin "2") (pinfunction "2_2") (pintype "passive"))
      (node (ref "J0") (pin "A21") (pinfunction "PGND_A21") (pintype "power_in"))
      (node (ref "J0") (pin "A22") (pinfunction "PGND_A22") (pintype "power_in"))
      (node (ref "J0") (pin "A23") (pinfunction "PGND_A23") (pintype "power_in"))
      (node (ref "J0") (pin "B21") (pinfunction "PGND_B21") (pintype "power_in"))
      (node (ref "J0") (pin "B22") (pinfunction "PGND_B22") (pintype "power_in"))
      (node (ref "J0") (pin "B23") (pinfunction "PGND_B23") (pintype "power_in"))
      (node (ref "J0") (pin "B24") (pinfunction "PGND_B24") (pintype "power_in"))
      (node (ref "J0") (pin "B25") (pinfunction "PGND_B25") (pintype "power_in"))
      (node (ref "J0") (pin "B26") (pinfunction "PGND_B26") (pintype "power_in"))
      (node (ref "J0") (pin "B27") (pinfunction "PGND_B27") (pintype "power_in"))
      (node (ref "J0") (pin "B28") (pinfunction "PGND_B28") (pintype "power_in"))
      (node (ref "J0") (pin "B29") (pinfunction "PGND_B29") (pintype "power_in"))
      (node (ref "J1") (pin "A21") (pinfunction "PGND_A21") (pintype "power_in"))
      (node (ref "J1") (pin "A22") (pinfunction "PGND_A22") (pintype "power_in"))
      (node (ref "J1") (pin "A23") (pinfunction "PGND_A23") (pintype "power_in"))
      (node (ref "J1") (pin "B21") (pinfunction "PGND_B21") (pintype "power_in"))
      (node (ref "J1") (pin "B22") (pinfunction "PGND_B22") (pintype "power_in"))
      (node (ref "J1") (pin "B23") (pinfunction "PGND_B23") (pintype "power_in"))
      (node (ref "J1") (pin "B24") (pinfunction "PGND_B24") (pintype "power_in"))
      (node (ref "J1") (pin "B25") (pinfunction "PGND_B25") (pintype "power_in"))
      (node (ref "J1") (pin "B26") (pinfunction "PGND_B26") (pintype "power_in"))
      (node (ref "J1") (pin "B27") (pinfunction "PGND_B27") (pintype "power_in"))
      (node (ref "J1") (pin "B28") (pinfunction "PGND_B28") (pintype "power_in"))
      (node (ref "J1") (pin "B29") (pinfunction "PGND_B29") (pintype "power_in"))
      (node (ref "J2") (pin "A21") (pinfunction "PGND_A21") (pintype "power_in"))
      (node (ref "J2") (pin "A22") (pinfunction "PGND_A22") (pintype "power_in"))
      (node (ref "J2") (pin "A23") (pinfunction "PGND_A23") (pintype "power_in"))
      (node (ref "J2") (pin "B21") (pinfunction "PGND_B21") (pintype "power_in"))
      (node (ref "J2") (pin "B22") (pinfunction "PGND_B22") (pintype "power_in"))
      (node (ref "J2") (pin "B23") (pinfunction "PGND_B23") (pintype "power_in"))
      (node (ref "J2") (pin "B24") (pinfunction "PGND_B24") (pintype "power_in"))
      (node (ref "J2") (pin "B25") (pinfunction "PGND_B25") (pintype "power_in"))
      (node (ref "J2") (pin "B26") (pinfunction "PGND_B26") (pintype "power_in"))
      (node (ref "J2") (pin "B27") (pinfunction "PGND_B27") (pintype "power_in"))
      (node (ref "J2") (pin "B28") (pinfunction "PGND_B28") (pintype "power_in"))
      (node (ref "J2") (pin "B29") (pinfunction "PGND_B29") (pintype "power_in"))
      (node (ref "J3") (pin "A21") (pinfunction "PGND_A21") (pintype "power_in"))
      (node (ref "J3") (pin "A22") (pinfunction "PGND_A22") (pintype "power_in"))
      (node (ref "J3") (pin "A23") (pinfunction "PGND_A23") (pintype "power_in"))
      (node (ref "J3") (pin "B21") (pinfunction "PGND_B21") (pintype "power_in"))
      (node (ref "J3") (pin "B22") (pinfunction "PGND_B22") (pintype "power_in"))
      (node (ref "J3") (pin "B23") (pinfunction "PGND_B23") (pintype "power_in"))
      (node (ref "J3") (pin "B24") (pinfunction "PGND_B24") (pintype "power_in"))
      (node (ref "J3") (pin "B25") (pinfunction "PGND_B25") (pintype "power_in"))
      (node (ref "J3") (pin "B26") (pinfunction "PGND_B26") (pintype "power_in"))
      (node (ref "J3") (pin "B27") (pinfunction "PGND_B27") (pintype "power_in"))
      (node (ref "J3") (pin "B28") (pinfunction "PGND_B28") (pintype "power_in"))
      (node (ref "J3") (pin "B29") (pinfunction "PGND_B29") (pintype "power_in"))
      (node (ref "J4") (pin "A21") (pinfunction "PGND_A21") (pintype "power_in"))
      (node (ref "J4") (pin "A22") (pinfunction "PGND_A22") (pintype "power_in"))
      (node (ref "J4") (pin "A23") (pinfunction "PGND_A23") (pintype "power_in"))
      (node (ref "J4") (pin "B21") (pinfunction "PGND_B21") (pintype "power_in"))
      (node (ref "J4") (pin "B22") (pinfunction "PGND_B22") (pintype "power_in"))
      (node (ref "J4") (pin "B23") (pinfunction "PGND_B23") (pintype "power_in"))
      (node (ref "J4") (pin "B24") (pinfunction "PGND_B24") (pintype "power_in"))
      (node (ref "J4") (pin "B25") (pinfunction "PGND_B25") (pintype "power_in"))
      (node (ref "J4") (pin "B26") (pinfunction "PGND_B26") (pintype "power_in"))
      (node (ref "J4") (pin "B27") (pinfunction "PGND_B27") (pintype "power_in"))
      (node (ref "J4") (pin "B28") (pinfunction "PGND_B28") (pintype "power_in"))
      (node (ref "J4") (pin "B29") (pinfunction "PGND_B29") (pintype "power_in"))
      (node (ref "R1") (pin "1") (pinfunction "1_1") (pintype "passive"))
      (node (ref "R2") (pin "1") (pinfunction "1_1") (pintype "passive"))
    )
    (net (code "34") (name "PR_3.3V-0") (class "Default")
      (node (ref "J0") (pin "A1") (pinfunction "PR_3.3V-0_A1") (pintype "power_in"))
      (node (ref "J0") (pin "B1") (pinfunction "PR_3.3V-0_B1") (pintype "power_in"))
      (node (ref "J1") (pin "A1") (pinfunction "PR_3.3V-0_A1") (pintype "power_in"))
      (node (ref "J1") (pin "B1") (pinfunction "PR_3.3V-0_B1") (pintype "power_in"))
      (node (ref "J2") (pin "A1") (pinfunction "PR_3.3V-0_A1") (pintype "power_in"))
      (node (ref "J2") (pin "B1") (pinfunction "PR_3.3V-0_B1") (pintype "power_in"))
      (node (ref "J3") (pin "A1") (pinfunction "PR_3.3V-0_A1") (pintype "power_in"))
      (node (ref "J3") (pin "B1") (pinfunction "PR_3.3V-0_B1") (pintype "power_in"))
      (node (ref "J4") (pin "A1") (pinfunction "PR_3.3V-0_A1") (pintype "power_in"))
      (node (ref "J4") (pin "B1") (pinfunction "PR_3.3V-0_B1") (pintype "power_in"))
    )
    (net (code "35") (name "PR_3.3V-1") (class "Default")
      (node (ref "J0") (pin "A2") (pinfunction "PR_3.3V-1_A2") (pintype "power_in"))
      (node (ref "J0") (pin "B2") (pinfunction "PR_3.3V-1_B2") (pintype "power_in"))
      (node (ref "J1") (pin "A2") (pinfunction "PR_3.3V-1_A2") (pintype "power_in"))
      (node (ref "J1") (pin "B2") (pinfunction "PR_3.3V-1_B2") (pintype "power_in"))
      (node (ref "J2") (pin "A2") (pinfunction "PR_3.3V-1_A2") (pintype "power_in"))
      (node (ref "J2") (pin "B2") (pinfunction "PR_3.3V-1_B2") (pintype "power_in"))
      (node (ref "J3") (pin "A2") (pinfunction "PR_3.3V-1_A2") (pintype "power_in"))
      (node (ref "J3") (pin "B2") (pinfunction "PR_3.3V-1_B2") (pintype "power_in"))
      (node (ref "J4") (pin "A2") (pinfunction "PR_3.3V-1_A2") (pintype "power_in"))
      (node (ref "J4") (pin "B2") (pinfunction "PR_3.3V-1_B2") (pintype "power_in"))
    )
    (net (code "36") (name "PR_3.3V-2") (class "Default")
      (node (ref "J0") (pin "A3") (pinfunction "PR_3.3V-2_A3") (pintype "power_in"))
      (node (ref "J0") (pin "B3") (pinfunction "PR_3.3V-2_B3") (pintype "power_in"))
      (node (ref "J1") (pin "A3") (pinfunction "PR_3.3V-2_A3") (pintype "power_in"))
      (node (ref "J1") (pin "B3") (pinfunction "PR_3.3V-2_B3") (pintype "power_in"))
      (node (ref "J2") (pin "A3") (pinfunction "PR_3.3V-2_A3") (pintype "power_in"))
      (node (ref "J2") (pin "B3") (pinfunction "PR_3.3V-2_B3") (pintype "power_in"))
      (node (ref "J3") (pin "A3") (pinfunction "PR_3.3V-2_A3") (pintype "power_in"))
      (node (ref "J3") (pin "B3") (pinfunction "PR_3.3V-2_B3") (pintype "power_in"))
      (node (ref "J4") (pin "A3") (pinfunction "PR_3.3V-2_A3") (pintype "power_in"))
      (node (ref "J4") (pin "B3") (pinfunction "PR_3.3V-2_B3") (pintype "power_in"))
    )
    (net (code "37") (name "PR_3.3V-3") (class "Default")
      (node (ref "J0") (pin "A4") (pinfunction "PR_3.3V-3_A4") (pintype "power_in"))
      (node (ref "J0") (pin "B4") (pinfunction "PR_3.3V-3_B4") (pintype "power_in"))
      (node (ref "J1") (pin "A4") (pinfunction "PR_3.3V-3_A4") (pintype "power_in"))
      (node (ref "J1") (pin "B4") (pinfunction "PR_3.3V-3_B4") (pintype "power_in"))
      (node (ref "J2") (pin "A4") (pinfunction "PR_3.3V-3_A4") (pintype "power_in"))
      (node (ref "J2") (pin "B4") (pinfunction "PR_3.3V-3_B4") (pintype "power_in"))
      (node (ref "J3") (pin "A4") (pinfunction "PR_3.3V-3_A4") (pintype "power_in"))
      (node (ref "J3") (pin "B4") (pinfunction "PR_3.3V-3_B4") (pintype "power_in"))
      (node (ref "J4") (pin "A4") (pinfunction "PR_3.3V-3_A4") (pintype "power_in"))
      (node (ref "J4") (pin "B4") (pinfunction "PR_3.3V-3_B4") (pintype "power_in"))
    )
    (net (code "38") (name "PR_3.3V-4") (class "Default")
      (node (ref "J0") (pin "A5") (pinfunction "PR_3.3V-4_A5") (pintype "power_in"))
      (node (ref "J0") (pin "B5") (pinfunction "PR_3.3V-4_B5") (pintype "power_in"))
      (node (ref "J1") (pin "A5") (pinfunction "PR_3.3V-4_A5") (pintype "power_in"))
      (node (ref "J1") (pin "B5") (pinfunction "PR_3.3V-4_B5") (pintype "power_in"))
      (node (ref "J2") (pin "A5") (pinfunction "PR_3.3V-4_A5") (pintype "power_in"))
      (node (ref "J2") (pin "B5") (pinfunction "PR_3.3V-4_B5") (pintype "power_in"))
      (node (ref "J3") (pin "A5") (pinfunction "PR_3.3V-4_A5") (pintype "power_in"))
      (node (ref "J3") (pin "B5") (pinfunction "PR_3.3V-4_B5") (pintype "power_in"))
      (node (ref "J4") (pin "A5") (pinfunction "PR_3.3V-4_A5") (pintype "power_in"))
      (node (ref "J4") (pin "B5") (pinfunction "PR_3.3V-4_B5") (pintype "power_in"))
    )
    (net (code "39") (name "PR_3.3V-5") (class "Default")
      (node (ref "J0") (pin "A6") (pinfunction "PR_3.3V-5_A6") (pintype "power_in"))
      (node (ref "J0") (pin "B6") (pinfunction "PR_3.3V-5_B6") (pintype "power_in"))
      (node (ref "J1") (pin "A6") (pinfunction "PR_3.3V-5_A6") (pintype "power_in"))
      (node (ref "J1") (pin "B6") (pinfunction "PR_3.3V-5_B6") (pintype "power_in"))
      (node (ref "J2") (pin "A6") (pinfunction "PR_3.3V-5_A6") (pintype "power_in"))
      (node (ref "J2") (pin "B6") (pinfunction "PR_3.3V-5_B6") (pintype "power_in"))
      (node (ref "J3") (pin "A6") (pinfunction "PR_3.3V-5_A6") (pintype "power_in"))
      (node (ref "J3") (pin "B6") (pinfunction "PR_3.3V-5_B6") (pintype "power_in"))
      (node (ref "J4") (pin "A6") (pinfunction "PR_3.3V-5_A6") (pintype "power_in"))
      (node (ref "J4") (pin "B6") (pinfunction "PR_3.3V-5_B6") (pintype "power_in"))
    )
    (net (code "40") (name "PR_3.3V-6") (class "Default")
      (node (ref "J0") (pin "A7") (pinfunction "PR_3.3V-6_A7") (pintype "power_in"))
      (node (ref "J0") (pin "B7") (pinfunction "PR_3.3V-6_B7") (pintype "power_in"))
      (node (ref "J1") (pin "A7") (pinfunction "PR_3.3V-6_A7") (pintype "power_in"))
      (node (ref "J1") (pin "B7") (pinfunction "PR_3.3V-6_B7") (pintype "power_in"))
      (node (ref "J2") (pin "A7") (pinfunction "PR_3.3V-6_A7") (pintype "power_in"))
      (node (ref "J2") (pin "B7") (pinfunction "PR_3.3V-6_B7") (pintype "power_in"))
      (node (ref "J3") (pin "A7") (pinfunction "PR_3.3V-6_A7") (pintype "power_in"))
      (node (ref "J3") (pin "B7") (pinfunction "PR_3.3V-6_B7") (pintype "power_in"))
      (node (ref "J4") (pin "A7") (pinfunction "PR_3.3V-6_A7") (pintype "power_in"))
      (node (ref "J4") (pin "B7") (pinfunction "PR_3.3V-6_B7") (pintype "power_in"))
    )
    (net (code "41") (name "PR_3.3V-7") (class "Default")
      (node (ref "J0") (pin "A8") (pinfunction "PR_3.3V-7_A8") (pintype "power_in"))
      (node (ref "J0") (pin "B8") (pinfunction "PR_3.3V-7_B8") (pintype "power_in"))
      (node (ref "J1") (pin "A8") (pinfunction "PR_3.3V-7_A8") (pintype "power_in"))
      (node (ref "J1") (pin "B8") (pinfunction "PR_3.3V-7_B8") (pintype "power_in"))
      (node (ref "J2") (pin "A8") (pinfunction "PR_3.3V-7_A8") (pintype "power_in"))
      (node (ref "J2") (pin "B8") (pinfunction "PR_3.3V-7_B8") (pintype "power_in"))
      (node (ref "J3") (pin "A8") (pinfunction "PR_3.3V-7_A8") (pintype "power_in"))
      (node (ref "J3") (pin "B8") (pinfunction "PR_3.3V-7_B8") (pintype "power_in"))
      (node (ref "J4") (pin "A8") (pinfunction "PR_3.3V-7_A8") (pintype "power_in"))
      (node (ref "J4") (pin "B8") (pinfunction "PR_3.3V-7_B8") (pintype "power_in"))
    )
    (net (code "42") (name "PR_3.3V-8") (class "Default")
      (node (ref "J0") (pin "A9") (pinfunction "PR_3.3V-8_A9") (pintype "power_in"))
      (node (ref "J0") (pin "B9") (pinfunction "PR_3.3V-8_B9") (pintype "power_in"))
      (node (ref "J1") (pin "A9") (pinfunction "PR_3.3V-8_A9") (pintype "power_in"))
      (node (ref "J1") (pin "B9") (pinfunction "PR_3.3V-8_B9") (pintype "power_in"))
      (node (ref "J2") (pin "A9") (pinfunction "PR_3.3V-8_A9") (pintype "power_in"))
      (node (ref "J2") (pin "B9") (pinfunction "PR_3.3V-8_B9") (pintype "power_in"))
      (node (ref "J3") (pin "A9") (pinfunction "PR_3.3V-8_A9") (pintype "power_in"))
      (node (ref "J3") (pin "B9") (pinfunction "PR_3.3V-8_B9") (pintype "power_in"))
      (node (ref "J4") (pin "A9") (pinfunction "PR_3.3V-8_A9") (pintype "power_in"))
      (node (ref "J4") (pin "B9") (pinfunction "PR_3.3V-8_B9") (pintype "power_in"))
    )
    (net (code "43") (name "PR_3.3V-9") (class "Default")
      (node (ref "J0") (pin "A10") (pinfunction "PR_3.3V-9_A10") (pintype "power_in"))
      (node (ref "J0") (pin "B10") (pinfunction "PR_3.3V-9_B10") (pintype "power_in"))
      (node (ref "J1") (pin "A10") (pinfunction "PR_3.3V-9_A10") (pintype "power_in"))
      (node (ref "J1") (pin "B10") (pinfunction "PR_3.3V-9_B10") (pintype "power_in"))
      (node (ref "J2") (pin "A10") (pinfunction "PR_3.3V-9_A10") (pintype "power_in"))
      (node (ref "J2") (pin "B10") (pinfunction "PR_3.3V-9_B10") (pintype "power_in"))
      (node (ref "J3") (pin "A10") (pinfunction "PR_3.3V-9_A10") (pintype "power_in"))
      (node (ref "J3") (pin "B10") (pinfunction "PR_3.3V-9_B10") (pintype "power_in"))
      (node (ref "J4") (pin "A10") (pinfunction "PR_3.3V-9_A10") (pintype "power_in"))
      (node (ref "J4") (pin "B10") (pinfunction "PR_3.3V-9_B10") (pintype "power_in"))
    )
    (net (code "44") (name "PR_3.3V-10") (class "Default")
      (node (ref "J0") (pin "A11") (pinfunction "PR_3.3V-10_A11") (pintype "power_in"))
      (node (ref "J0") (pin "B11") (pinfunction "PR_3.3V-10_B11") (pintype "power_in"))
      (node (ref "J1") (pin "A11") (pinfunction "PR_3.3V-10_A11") (pintype "power_in"))
      (node (ref "J1") (pin "B11") (pinfunction "PR_3.3V-10_B11") (pintype "power_in"))
      (node (ref "J2") (pin "A11") (pinfunction "PR_3.3V-10_A11") (pintype "power_in"))
      (node (ref "J2") (pin "B11") (pinfunction "PR_3.3V-10_B11") (pintype "power_in"))
      (node (ref "J3") (pin "A11") (pinfunction "PR_3.3V-10_A11") (pintype "power_in"))
      (node (ref "J3") (pin "B11") (pinfunction "PR_3.3V-10_B11") (pintype "power_in"))
      (node (ref "J4") (pin "A11") (pinfunction "PR_3.3V-10_A11") (pintype "power_in"))
      (node (ref "J4") (pin "B11") (pinfunction "PR_3.3V-10_B11") (pintype "power_in"))
    )
    (net (code "45") (name "PR_3.3V-11") (class "Default")
      (node (ref "J0") (pin "A12") (pinfunction "PR_3.3V-11_A12") (pintype "power_in"))
      (node (ref "J0") (pin "B12") (pinfunction "PR_3.3V-11_B12") (pintype "power_in"))
      (node (ref "J1") (pin "A12") (pinfunction "PR_3.3V-11_A12") (pintype "power_in"))
      (node (ref "J1") (pin "B12") (pinfunction "PR_3.3V-11_B12") (pintype "power_in"))
      (node (ref "J2") (pin "A12") (pinfunction "PR_3.3V-11_A12") (pintype "power_in"))
      (node (ref "J2") (pin "B12") (pinfunction "PR_3.3V-11_B12") (pintype "power_in"))
      (node (ref "J3") (pin "A12") (pinfunction "PR_3.3V-11_A12") (pintype "power_in"))
      (node (ref "J3") (pin "B12") (pinfunction "PR_3.3V-11_B12") (pintype "power_in"))
      (node (ref "J4") (pin "A12") (pinfunction "PR_3.3V-11_A12") (pintype "power_in"))
      (node (ref "J4") (pin "B12") (pinfunction "PR_3.3V-11_B12") (pintype "power_in"))
    )
    (net (code "46") (name "PR_3.3V-12") (class "Default")
      (node (ref "J0") (pin "A13") (pinfunction "PR_3.3V-12_A13") (pintype "power_in"))
      (node (ref "J0") (pin "B13") (pinfunction "PR_3.3V-12_B13") (pintype "power_in"))
      (node (ref "J1") (pin "A13") (pinfunction "PR_3.3V-12_A13") (pintype "power_in"))
      (node (ref "J1") (pin "B13") (pinfunction "PR_3.3V-12_B13") (pintype "power_in"))
      (node (ref "J2") (pin "A13") (pinfunction "PR_3.3V-12_A13") (pintype "power_in"))
      (node (ref "J2") (pin "B13") (pinfunction "PR_3.3V-12_B13") (pintype "power_in"))
      (node (ref "J3") (pin "A13") (pinfunction "PR_3.3V-12_A13") (pintype "power_in"))
      (node (ref "J3") (pin "B13") (pinfunction "PR_3.3V-12_B13") (pintype "power_in"))
      (node (ref "J4") (pin "A13") (pinfunction "PR_3.3V-12_A13") (pintype "power_in"))
      (node (ref "J4") (pin "B13") (pinfunction "PR_3.3V-12_B13") (pintype "power_in"))
    )
    (net (code "47") (name "PR_BATT-0") (class "Default")
      (node (ref "J0") (pin "A14") (pinfunction "PR_BATT-0_A14") (pintype "power_in"))
      (node (ref "J0") (pin "B14") (pinfunction "PR_BATT-0_B14") (pintype "power_in"))
      (node (ref "J1") (pin "A14") (pinfunction "PR_BATT-0_A14") (pintype "power_in"))
      (node (ref "J1") (pin "B14") (pinfunction "PR_BATT-0_B14") (pintype "power_in"))
      (node (ref "J2") (pin "A14") (pinfunction "PR_BATT-0_A14") (pintype "power_in"))
      (node (ref "J2") (pin "B14") (pinfunction "PR_BATT-0_B14") (pintype "power_in"))
      (node (ref "J3") (pin "A14") (pinfunction "PR_BATT-0_A14") (pintype "power_in"))
      (node (ref "J3") (pin "B14") (pinfunction "PR_BATT-0_B14") (pintype "power_in"))
      (node (ref "J4") (pin "A14") (pinfunction "PR_BATT-0_A14") (pintype "power_in"))
      (node (ref "J4") (pin "B14") (pinfunction "PR_BATT-0_B14") (pintype "power_in"))
    )
    (net (code "48") (name "PR_BATT-1") (class "Default")
      (node (ref "J0") (pin "A15") (pinfunction "PR_BATT-1_A15") (pintype "power_in"))
      (node (ref "J0") (pin "B15") (pinfunction "PR_BATT-1_B15") (pintype "power_in"))
      (node (ref "J1") (pin "A15") (pinfunction "PR_BATT-1_A15") (pintype "power_in"))
      (node (ref "J1") (pin "B15") (pinfunction "PR_BATT-1_B15") (pintype "power_in"))
      (node (ref "J2") (pin "A15") (pinfunction "PR_BATT-1_A15") (pintype "power_in"))
      (node (ref "J2") (pin "B15") (pinfunction "PR_BATT-1_B15") (pintype "power_in"))
      (node (ref "J3") (pin "A15") (pinfunction "PR_BATT-1_A15") (pintype "power_in"))
      (node (ref "J3") (pin "B15") (pinfunction "PR_BATT-1_B15") (pintype "power_in"))
      (node (ref "J4") (pin "A15") (pinfunction "PR_BATT-1_A15") (pintype "power_in"))
      (node (ref "J4") (pin "B15") (pinfunction "PR_BATT-1_B15") (pintype "power_in"))
    )
    (net (code "49") (name "PR_BATT-2") (class "Default")
      (node (ref "J0") (pin "A16") (pinfunction "PR_BATT-2_A16") (pintype "power_in"))
      (node (ref "J0") (pin "B16") (pinfunction "PR_BATT-2_B16") (pintype "power_in"))
      (node (ref "J1") (pin "A16") (pinfunction "PR_BATT-2_A16") (pintype "power_in"))
      (node (ref "J1") (pin "B16") (pinfunction "PR_BATT-2_B16") (pintype "power_in"))
      (node (ref "J2") (pin "A16") (pinfunction "PR_BATT-2_A16") (pintype "power_in"))
      (node (ref "J2") (pin "B16") (pinfunction "PR_BATT-2_B16") (pintype "power_in"))
      (node (ref "J3") (pin "A16") (pinfunction "PR_BATT-2_A16") (pintype "power_in"))
      (node (ref "J3") (pin "B16") (pinfunction "PR_BATT-2_B16") (pintype "power_in"))
      (node (ref "J4") (pin "A16") (pinfunction "PR_BATT-2_A16") (pintype "power_in"))
      (node (ref "J4") (pin "B16") (pinfunction "PR_BATT-2_B16") (pintype "power_in"))
    )
    (net (code "50") (name "PR_BATT-3") (class "Default")
      (node (ref "J0") (pin "A17") (pinfunction "PR_BATT-3_A17") (pintype "power_in"))
      (node (ref "J0") (pin "B17") (pinfunction "PR_BATT-3_B17") (pintype "power_in"))
      (node (ref "J1") (pin "A17") (pinfunction "PR_BATT-3_A17") (pintype "power_in"))
      (node (ref "J1") (pin "B17") (pinfunction "PR_BATT-3_B17") (pintype "power_in"))
      (node (ref "J2") (pin "A17") (pinfunction "PR_BATT-3_A17") (pintype "power_in"))
      (node (ref "J2") (pin "B17") (pinfunction "PR_BATT-3_B17") (pintype "power_in"))
      (node (ref "J3") (pin "A17") (pinfunction "PR_BATT-3_A17") (pintype "power_in"))
      (node (ref "J3") (pin "B17") (pinfunction "PR_BATT-3_B17") (pintype "power_in"))
      (node (ref "J4") (pin "A17") (pinfunction "PR_BATT-3_A17") (pintype "power_in"))
      (node (ref "J4") (pin "B17") (pinfunction "PR_BATT-3_B17") (pintype "power_in"))
    )
    (net (code "51") (name "PR_BATT-4") (class "Default")
      (node (ref "J0") (pin "A18") (pinfunction "PR_BATT-4_A18") (pintype "power_in"))
      (node (ref "J0") (pin "B18") (pinfunction "PR_BATT-4_B18") (pintype "power_in"))
      (node (ref "J1") (pin "A18") (pinfunction "PR_BATT-4_A18") (pintype "power_in"))
      (node (ref "J1") (pin "B18") (pinfunction "PR_BATT-4_B18") (pintype "power_in"))
      (node (ref "J2") (pin "A18") (pinfunction "PR_BATT-4_A18") (pintype "power_in"))
      (node (ref "J2") (pin "B18") (pinfunction "PR_BATT-4_B18") (pintype "power_in"))
      (node (ref "J3") (pin "A18") (pinfunction "PR_BATT-4_A18") (pintype "power_in"))
      (node (ref "J3") (pin "B18") (pinfunction "PR_BATT-4_B18") (pintype "power_in"))
      (node (ref "J4") (pin "A18") (pinfunction "PR_BATT-4_A18") (pintype "power_in"))
      (node (ref "J4") (pin "B18") (pinfunction "PR_BATT-4_B18") (pintype "power_in"))
    )
    (net (code "52") (name "PR_BATT-5") (class "Default")
      (node (ref "J0") (pin "A19") (pinfunction "PR_BATT-5_A19") (pintype "power_in"))
      (node (ref "J0") (pin "B19") (pinfunction "PR_BATT-5_B19") (pintype "power_in"))
      (node (ref "J1") (pin "A19") (pinfunction "PR_BATT-5_A19") (pintype "power_in"))
      (node (ref "J1") (pin "B19") (pinfunction "PR_BATT-5_B19") (pintype "power_in"))
      (node (ref "J2") (pin "A19") (pinfunction "PR_BATT-5_A19") (pintype "power_in"))
      (node (ref "J2") (pin "B19") (pinfunction "PR_BATT-5_B19") (pintype "power_in"))
      (node (ref "J3") (pin "A19") (pinfunction "PR_BATT-5_A19") (pintype "power_in"))
      (node (ref "J3") (pin "B19") (pinfunction "PR_BATT-5_B19") (pintype "power_in"))
      (node (ref "J4") (pin "A19") (pinfunction "PR_BATT-5_A19") (pintype "power_in"))
      (node (ref "J4") (pin "B19") (pinfunction "PR_BATT-5_B19") (pintype "power_in"))
    )
    (net (code "53") (name "PR_BATT-6") (class "Default")
      (node (ref "J0") (pin "A20") (pinfunction "PR_BATT-6_A20") (pintype "power_in"))
      (node (ref "J0") (pin "B20") (pinfunction "PR_BATT-6_B20") (pintype "power_in"))
      (node (ref "J1") (pin "A20") (pinfunction "PR_BATT-6_A20") (pintype "power_in"))
      (node (ref "J1") (pin "B20") (pinfunction "PR_BATT-6_B20") (pintype "power_in"))
      (node (ref "J2") (pin "A20") (pinfunction "PR_BATT-6_A20") (pintype "power_in"))
      (node (ref "J2") (pin "B20") (pinfunction "PR_BATT-6_B20") (pintype "power_in"))
      (node (ref "J3") (pin "A20") (pinfunction "PR_BATT-6_A20") (pintype "power_in"))
      (node (ref "J3") (pin "B20") (pinfunction "PR_BATT-6_B20") (pintype "power_in"))
      (node (ref "J4") (pin "A20") (pinfunction "PR_BATT-6_A20") (pintype "power_in"))
      (node (ref "J4") (pin "B20") (pinfunction "PR_BATT-6_B20") (pintype "power_in"))
    )
    (net (code "54") (name "PWR_CTRL_SW") (class "Default")
      (node (ref "J0") (pin "A40") (pinfunction "PWR_CTRL_SW_A40") (pintype "bidirectional"))
      (node (ref "J0") (pin "B40") (pinfunction "PWR_CTRL_SW_B40") (pintype "bidirectional"))
      (node (ref "J1") (pin "A40") (pinfunction "PWR_CTRL_SW_A40") (pintype "bidirectional"))
      (node (ref "J1") (pin "B40") (pinfunction "PWR_CTRL_SW_B40") (pintype "bidirectional"))
      (node (ref "J2") (pin "A40") (pinfunction "PWR_CTRL_SW_A40") (pintype "bidirectional"))
      (node (ref "J2") (pin "B40") (pinfunction "PWR_CTRL_SW_B40") (pintype "bidirectional"))
      (node (ref "J3") (pin "A40") (pinfunction "PWR_CTRL_SW_A40") (pintype "bidirectional"))
      (node (ref "J3") (pin "B40") (pinfunction "PWR_CTRL_SW_B40") (pintype "bidirectional"))
      (node (ref "J4") (pin "A40") (pinfunction "PWR_CTRL_SW_A40") (pintype "bidirectional"))
      (node (ref "J4") (pin "B40") (pinfunction "PWR_CTRL_SW_B40") (pintype "bidirectional"))
    )
  )
)
